# WX0_010_827DL.net
KiCad netlist of a schematic drawn in Altium Designer
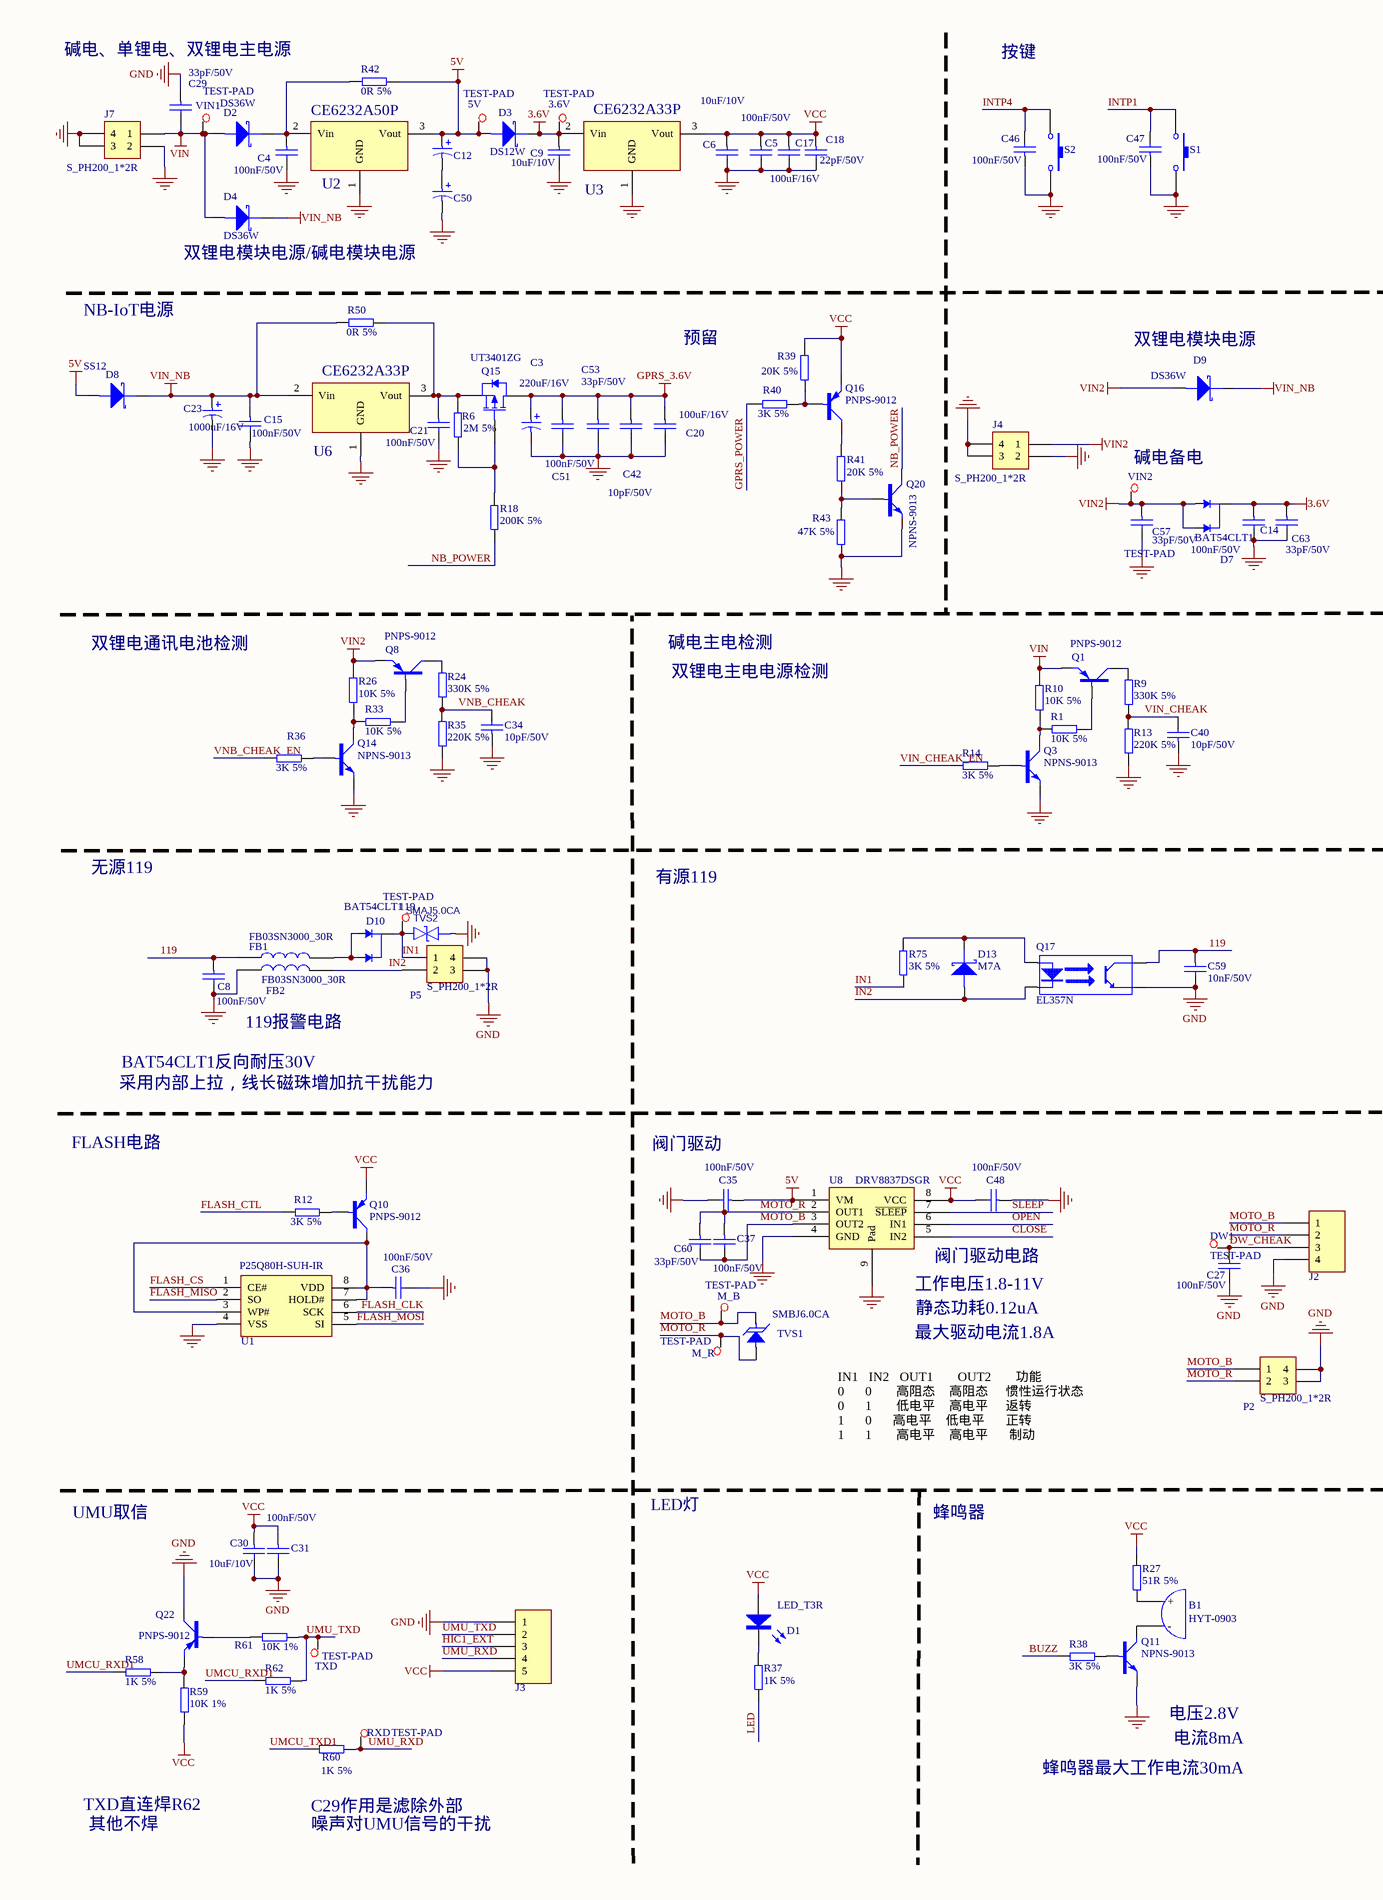
[diagram p0: WX0.010.827DL.SchDoc, left]
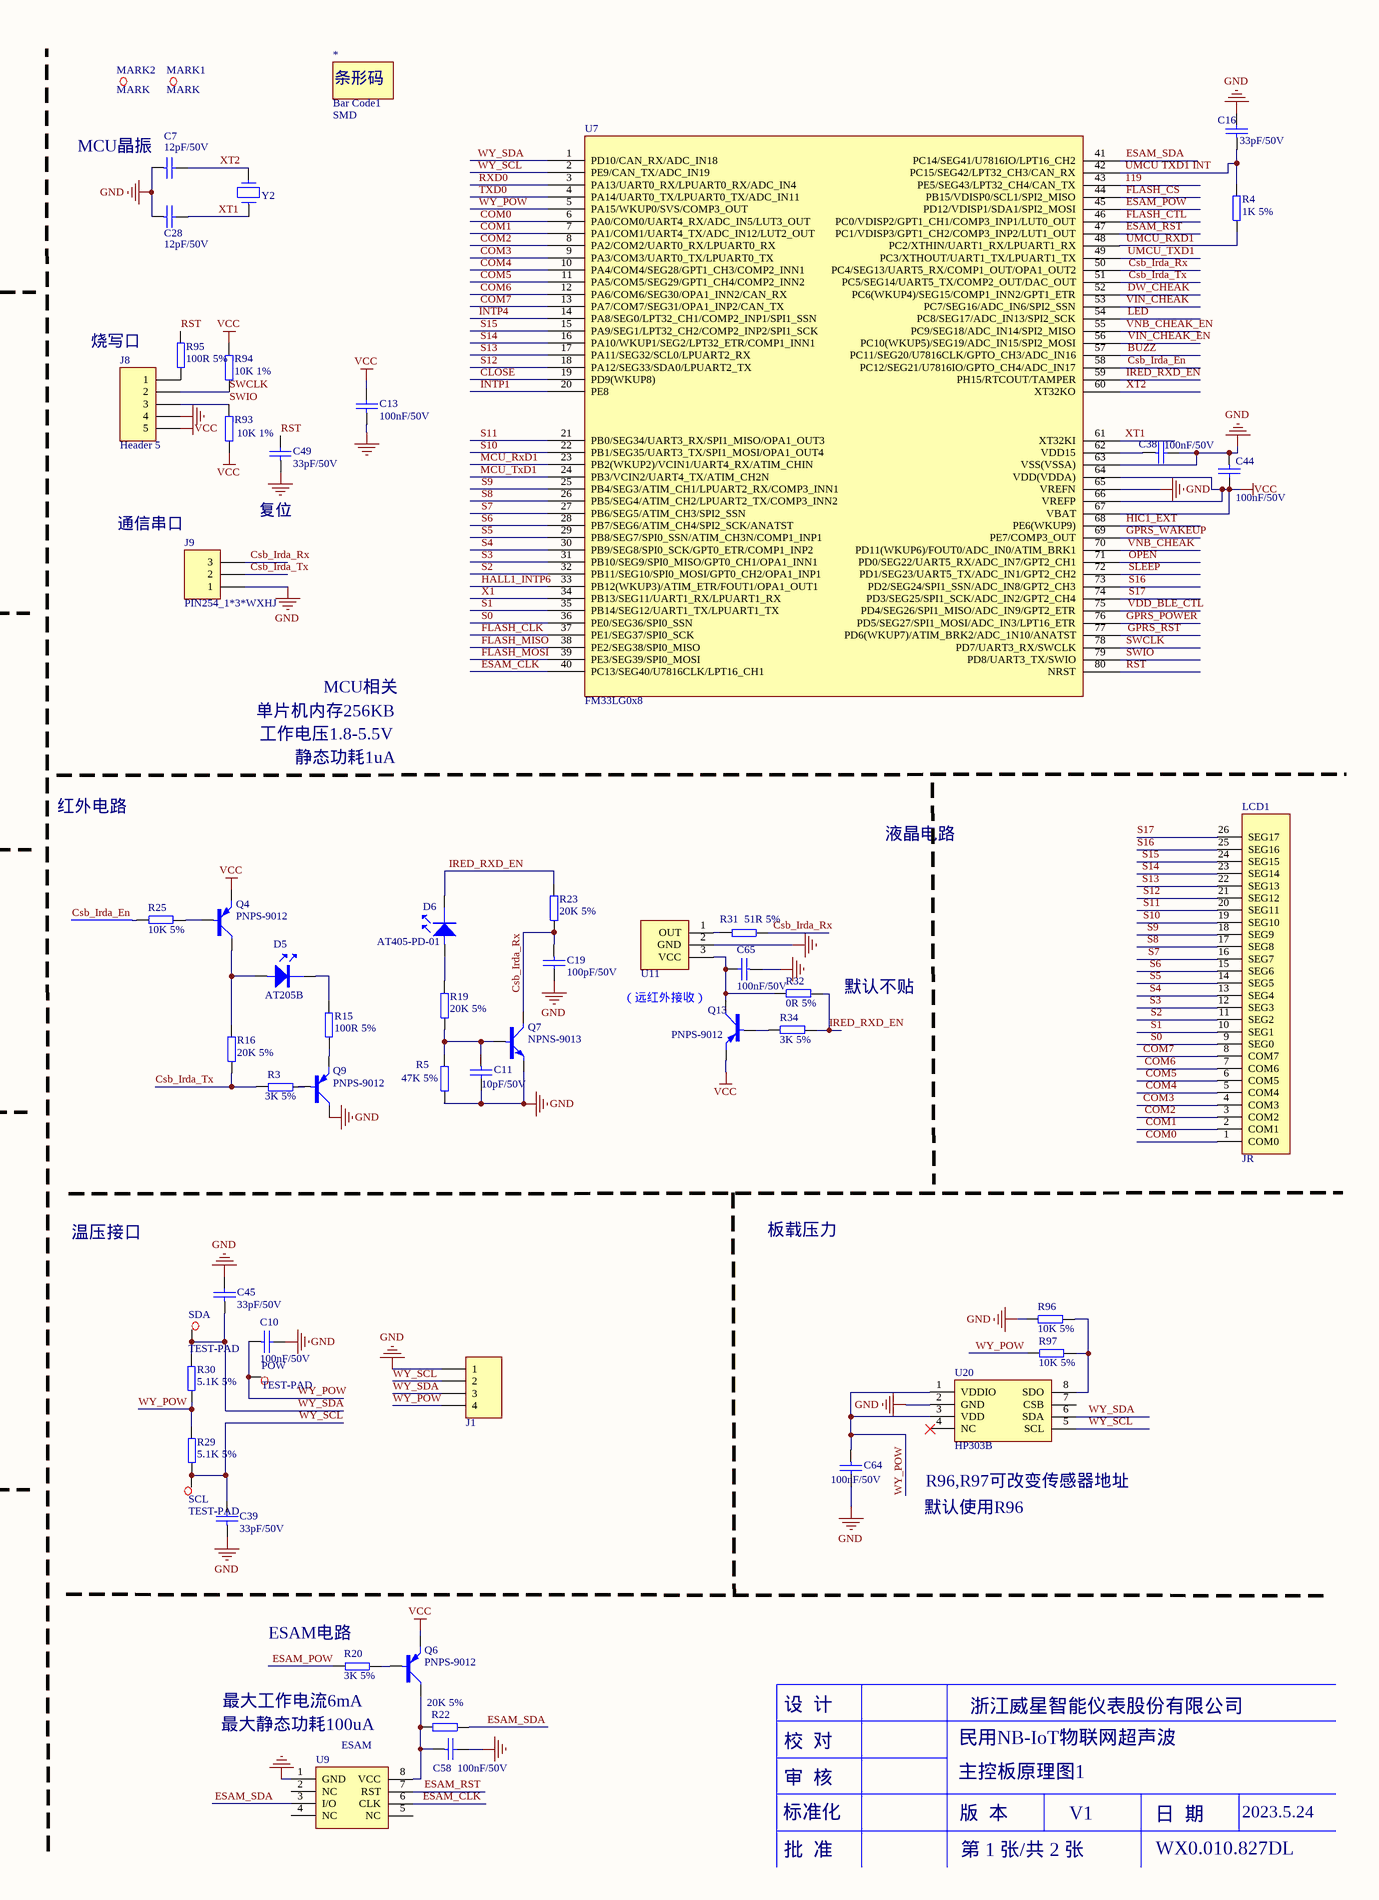
[diagram p1: WX0.010.827DL.SchDoc, right]

(export (version "E")
  (design (tool "Eeschema 10.0.6"))
  (components
    (comp (ref "*")
      (value "Bar Code1")
      (footprint "Bar Code1")
      (description "条形码 ,填充，无需焊接器件")
      (fields (field (name "PART NUMBER") "AD_WXHJ_Bar Code_02") (field (name "SMD/DIP") "SMD"))
      (libsource (lib "Database_Libs2") (part "05_AD_WXHJ_Bar Code_02"))
    )
    (comp (ref "3.6V")
      (value "TEST-PAD")
      (footprint "TEST-PAD")
      (description "单面焊盘测试点")
      (fields (field (name "PART NUMBER") "AD_WXHJ_TEST-PAD_01"))
      (libsource (lib "Database_Libs2") (part "TEST-PAD"))
    )
    (comp (ref "5V")
      (value "TEST-PAD")
      (footprint "TEST-PAD")
      (description "单面焊盘测试点")
      (fields (field (name "PART NUMBER") "AD_WXHJ_TEST-PAD_01"))
      (libsource (lib "Database_Libs2") (part "TEST-PAD"))
    )
    (comp (ref "119")
      (value "TEST-PAD")
      (footprint "TEST-PAD")
      (description "单面焊盘测试点")
      (fields (field (name "PART NUMBER") "AD_WXHJ_TEST-PAD_01"))
      (libsource (lib "Database_Libs2") (part "TEST-PAD"))
    )
    (comp (ref "B1")
      (value "HYT-0903")
      (footprint "HYT-0903")
      (description "直插,直径9mm,高5.5mm,5 V,2 V,30 mA,兴化市华宇电子有限公司,HYT-0903")
      (fields (field (name "PART NUMBER") "1010602-0007"))
      (libsource (lib "Database_Libs2") (part "07_HYT-0903"))
    )
    (comp (ref "C3")
      (value "220uF/16V")
      (footprint "220uf")
      (description "220UF")
      (fields (field (name "PART NUMBER") "1010203-0026"))
      (libsource (lib "Database_Libs2") (part "CAL7MRZLH_1000U_R"))
    )
    (comp (ref "C4")
      (value "100nF/50V")
      (footprint "CAP0603")
      (description "104pF,50 V,±10%,0603,国巨,CC0603KRX7R9BB104")
      (fields (field (name "PART NUMBER") "101020103-0021"))
      (libsource (lib "Database_Libs2") (part "CC03K7R9_100N"))
    )
    (comp (ref "C5")
      (value "100nF/50V")
      (footprint "CAP0603")
      (description "104pF,50 V,±10%,0603,国巨,CC0603KRX7R9BB104")
      (fields (field (name "PART NUMBER") "101020103-0021"))
      (libsource (lib "Database_Libs2") (part "CC03K7R9_100N"))
    )
    (comp (ref "C6")
      (value "10uF/10V")
      (footprint "CAP0603")
      (description "106pF,10 V,±10%,0603,村田,GRM188R61A106KE47D")
      (fields (field (name "PART NUMBER") "101020103-0026"))
      (libsource (lib "Database_Libs2") (part "CC03K5R6_10U"))
    )
    (comp (ref "C7")
      (value "12pF/50V")
      (footprint "CAP0603")
      (description "12P,50 V,±5%,0603,国巨,CC0603JRNPO9BN12")
      (fields (field (name "PART NUMBER") "101020103-0005"))
      (libsource (lib "Database_Libs2") (part "CC03JPO9_12P"))
    )
    (comp (ref "C8")
      (value "100nF/50V")
      (footprint "CAP0603")
      (description "104pF,50 V,±10%,0603,国巨,CC0603KRX7R9BB104")
      (fields (field (name "PART NUMBER") "101020103-0021"))
      (libsource (lib "Database_Libs2") (part "CC03K7R9_100N"))
    )
    (comp (ref "C9")
      (value "10uF/10V")
      (footprint "CAP0603")
      (description "106pF,10 V,±10%,0603,村田,GRM188R61A106KE47D")
      (fields (field (name "PART NUMBER") "101020103-0026"))
      (libsource (lib "Database_Libs2") (part "CC03K5R6_10U"))
    )
    (comp (ref "C10")
      (value "100nF/50V")
      (footprint "CAP0603")
      (description "104pF,50 V,±10%,0603,国巨,CC0603KRX7R9BB104")
      (fields (field (name "PART NUMBER") "101020103-0021"))
      (libsource (lib "Database_Libs2") (part "CC03K7R9_100N"))
    )
    (comp (ref "C11")
      (value "10pF/50V")
      (footprint "CAP0603")
      (description "10pF,50 V,±5%,0603,X7R,国巨,CC0603JRNPO9BN100")
      (fields (field (name "PART NUMBER") "101020103-0014"))
      (libsource (lib "Database_Libs2") (part "CC03JPO9_10P"))
    )
    (comp (ref "C12")
      (value "1000uF/16V")
      (footprint "CAPPC_350_800_1200")
      (description "1000uF,16 V,±20%,8*20mm,Rubycon,16ZLH1000M")
      (fields (field (name "PART NUMBER") "1010203-0029"))
      (libsource (lib "Database_Libs2") (part "CAL7MRZLH_1000U_R"))
    )
    (comp (ref "C13")
      (value "100nF/50V")
      (footprint "CAP0603")
      (description "104pF,50 V,±10%,0603,国巨,CC0603KRX7R9BB104")
      (fields (field (name "PART NUMBER") "101020103-0021"))
      (libsource (lib "Database_Libs2") (part "CC03K7R9_100N"))
    )
    (comp (ref "C14")
      (value "100nF/50V")
      (footprint "CAP0603")
      (description "104pF,50 V,±10%,0603,国巨,CC0603KRX7R9BB104")
      (fields (field (name "PART NUMBER") "101020103-0021"))
      (libsource (lib "Database_Libs2") (part "CC03K7R9_100N"))
    )
    (comp (ref "C15")
      (value "100nF/50V")
      (footprint "CAP0603")
      (description "104pF,50 V,±10%,0603,国巨,CC0603KRX7R9BB104")
      (fields (field (name "PART NUMBER") "101020103-0021"))
      (libsource (lib "Database_Libs2") (part "CC03K7R9_100N"))
    )
    (comp (ref "C16")
      (value "33pF/50V")
      (footprint "CAP0603")
      (description "33pF,50 V,±10%,0603,国巨,CC0603KRNPO9BN33")
      (fields (field (name "PART NUMBER") "101020103-0027"))
      (libsource (lib "Database_Libs2") (part "CC03KPO9_33P"))
    )
    (comp (ref "C17")
      (value "100uF/16V")
      (footprint "GRM31CR60J107ME39L")
      (description "100u,16 V,±10%,1206,国巨,CC1206KRNPO7BN106P")
      (libsource (lib "Database_Libs2") (part "CC06KPO7_106P"))
    )
    (comp (ref "C18")
      (value "22pF/50V")
      (footprint "CAP0603")
      (description "22pF,50 V,±5%,0603,国巨,CC0603JRNPO9BN22")
      (fields (field (name "PART NUMBER") "101020103-0009"))
      (libsource (lib "Database_Libs2") (part "CC03JPO9_22P"))
    )
    (comp (ref "C19")
      (value "100pF/50V")
      (footprint "CAP0603")
      (description "101pf,50 V,±5%,0603,国巨,CC0603JRNP09BN101")
      (fields (field (name "PART NUMBER") "101020103-0010"))
      (libsource (lib "Database_Libs2") (part "CC03JPO9_101P"))
    )
    (comp (ref "C20")
      (value "100uF/16V")
      (footprint "GRM31CR60J107ME39L")
      (libsource (lib "Database_Libs2") (part "CC06KPO7_106P"))
    )
    (comp (ref "C21")
      (value "100nF/50V")
      (footprint "CAP0603")
      (description "104pF,50 V,±10%,0603,国巨,CC0603KRX7R9BB104")
      (fields (field (name "PART NUMBER") "101020103-0021"))
      (libsource (lib "Database_Libs2") (part "CC03K7R9_100N"))
    )
    (comp (ref "C23")
      (value "1000uF/16V")
      (footprint "CAPSM_450_1000_1050")
      (description "1000UF,16V,±20%,贴片10*10.2MM,深圳市三炎科电子科技有限公司,16V1000UF")
      (fields (field (name "PART NUMBER") "1010203-0026"))
      (libsource (lib "Database_Libs2") (part "CAL7MRZLH_1000U_R"))
    )
    (comp (ref "C27")
      (value "100nF/50V")
      (footprint "CAP0603")
      (description "104pF,50 V,±10%,0603,国巨,CC0603KRX7R9BB104")
      (fields (field (name "PART NUMBER") "101020103-0021"))
      (libsource (lib "Database_Libs2") (part "CC03K7R9_100N"))
    )
    (comp (ref "C28")
      (value "12pF/50V")
      (footprint "CAP0603")
      (description "12P,50 V,±5%,0603,国巨,CC0603JRNPO9BN12")
      (fields (field (name "PART NUMBER") "101020103-0005"))
      (libsource (lib "Database_Libs2") (part "CC03JPO9_12P"))
    )
    (comp (ref "C29")
      (value "33pF/50V")
      (footprint "CAP0603")
      (description "33pF,50 V,±10%,0603,国巨,CC0603KRNPO9BN33")
      (fields (field (name "PART NUMBER") "101020103-0027"))
      (libsource (lib "Database_Libs2") (part "CC03KPO9_33P"))
    )
    (comp (ref "C30")
      (value "10uF/10V")
      (footprint "CAP0603")
      (description "106pF,10 V,±10%,0603,村田,GRM188R61A106KE47D")
      (fields (field (name "PART NUMBER") "101020103-0026"))
      (libsource (lib "Database_Libs2") (part "CC03K5R6_10U"))
    )
    (comp (ref "C31")
      (value "100nF/50V")
      (footprint "CAP0603")
      (description "104pF,50 V,±10%,0603,国巨,CC0603KRX7R9BB104")
      (fields (field (name "PART NUMBER") "101020103-0021"))
      (libsource (lib "Database_Libs2") (part "CC03K7R9_100N"))
    )
    (comp (ref "C34")
      (value "10pF/50V")
      (footprint "CAP0603")
      (description "10pF,50 V,±5%,0603,X7R,国巨,CC0603JRNPO9BN100")
      (fields (field (name "PART NUMBER") "101020103-0014"))
      (libsource (lib "Database_Libs2") (part "CC03JPO9_10P"))
    )
    (comp (ref "C35")
      (value "100nF/50V")
      (footprint "CAP0603")
      (description "104pF,50 V,±10%,0603,国巨,CC0603KRX7R9BB104")
      (fields (field (name "PART NUMBER") "101020103-0021"))
      (libsource (lib "Database_Libs2") (part "CC03K7R9_100N"))
    )
    (comp (ref "C36")
      (value "100nF/50V")
      (footprint "CAP0603")
      (description "104pF,50 V,±10%,0603,国巨,CC0603KRX7R9BB104")
      (fields (field (name "PART NUMBER") "101020103-0021"))
      (libsource (lib "Database_Libs2") (part "CC03K7R9_100N"))
    )
    (comp (ref "C37")
      (value "100nF/50V")
      (footprint "CAP0603")
      (description "104pF,50 V,±10%,0603,国巨,CC0603KRX7R9BB104")
      (fields (field (name "PART NUMBER") "101020103-0021"))
      (libsource (lib "Database_Libs2") (part "CC03K7R9_100N"))
    )
    (comp (ref "C38")
      (value "100nF/50V")
      (footprint "CAP0603")
      (description "104pF,50 V,±10%,0603,国巨,CC0603KRX7R9BB104")
      (fields (field (name "PART NUMBER") "101020103-0021"))
      (libsource (lib "Database_Libs2") (part "CC03K7R9_100N"))
    )
    (comp (ref "C39")
      (value "33pF/50V")
      (footprint "CAP0603")
      (description "33pF,50 V,±10%,0603,国巨,CC0603KRNPO9BN33")
      (fields (field (name "PART NUMBER") "101020103-0027"))
      (libsource (lib "Database_Libs2") (part "CC03KPO9_33P"))
    )
    (comp (ref "C40")
      (value "10pF/50V")
      (footprint "CAP0603")
      (description "10pF,50 V,±5%,0603,X7R,国巨,CC0603JRNPO9BN100")
      (fields (field (name "PART NUMBER") "101020103-0014"))
      (libsource (lib "Database_Libs2") (part "CC03JPO9_10P"))
    )
    (comp (ref "C42")
      (value "10pF/50V")
      (footprint "CAP0603")
      (description "10pF,50 V,±5%,0603,X7R,国巨,CC0603JRNPO9BN100")
      (fields (field (name "PART NUMBER") "101020103-0014"))
      (libsource (lib "Database_Libs2") (part "CC03JPO9_10P"))
    )
    (comp (ref "C44")
      (value "100nF/50V")
      (footprint "CAP0603")
      (description "104pF,50 V,±10%,0603,国巨,CC0603KRX7R9BB104")
      (fields (field (name "PART NUMBER") "101020103-0021"))
      (libsource (lib "Database_Libs2") (part "CC03K7R9_100N"))
    )
    (comp (ref "C45")
      (value "33pF/50V")
      (footprint "CAP0603")
      (description "33pF,50 V,±10%,0603,国巨,CC0603KRNPO9BN33")
      (fields (field (name "PART NUMBER") "101020103-0027"))
      (libsource (lib "Database_Libs2") (part "CC03KPO9_33P"))
    )
    (comp (ref "C46")
      (value "100nF/50V")
      (footprint "CAP0603")
      (description "104pF,50 V,±10%,0603,国巨,CC0603KRX7R9BB104")
      (fields (field (name "PART NUMBER") "101020103-0021"))
      (libsource (lib "Database_Libs2") (part "CC03K7R9_100N"))
    )
    (comp (ref "C47")
      (value "100nF/50V")
      (footprint "CAP0603")
      (description "104pF,50 V,±10%,0603,国巨,CC0603KRX7R9BB104")
      (fields (field (name "PART NUMBER") "101020103-0021"))
      (libsource (lib "Database_Libs2") (part "CC03K7R9_100N"))
    )
    (comp (ref "C48")
      (value "100nF/50V")
      (footprint "CAP0603")
      (description "104pF,50 V,±10%,0603,国巨,CC0603KRX7R9BB104")
      (fields (field (name "PART NUMBER") "101020103-0021"))
      (libsource (lib "Database_Libs2") (part "CC03K7R9_100N"))
    )
    (comp (ref "C49")
      (value "33pF/50V")
      (footprint "CAP0603")
      (description "33pF,50 V,±10%,0603,国巨,CC0603KRNPO9BN33")
      (fields (field (name "PART NUMBER") "101020103-0027"))
      (libsource (lib "Database_Libs2") (part "CC03KPO9_33P"))
    )
    (comp (ref "C50")
      (value "1000uF/16V")
      (footprint "CAPPC_350_800_1200")
      (description "1000uF,16 V,±20%,8*20mm,Rubycon,16ZLH1000M")
      (fields (field (name "PART NUMBER") "1010203-0029"))
      (libsource (lib "Database_Libs2") (part "CAL7MRZLH_1000U_R"))
    )
    (comp (ref "C51")
      (value "100nF/50V")
      (footprint "CAP0603")
      (description "104pF,50 V,±10%,0603,国巨,CC0603KRX7R9BB104")
      (fields (field (name "PART NUMBER") "101020103-0021"))
      (libsource (lib "Database_Libs2") (part "CC03K7R9_100N"))
    )
    (comp (ref "C53")
      (value "33pF/50V")
      (footprint "CAP0603")
      (description "33pF,50 V,±10%,0603,国巨,CC0603KRNPO9BN33")
      (fields (field (name "PART NUMBER") "101020103-0027"))
      (libsource (lib "Database_Libs2") (part "CC03KPO9_33P"))
    )
    (comp (ref "C57")
      (value "33pF/50V")
      (footprint "CAP0603")
      (description "33pF,50 V,±10%,0603,国巨,CC0603KRNPO9BN33")
      (fields (field (name "PART NUMBER") "101020103-0027"))
      (libsource (lib "Database_Libs2") (part "CC03KPO9_33P"))
    )
    (comp (ref "C58")
      (value "100nF/50V")
      (footprint "CAP0603")
      (description "104pF,50 V,±10%,0603,国巨,CC0603KRX7R9BB104")
      (fields (field (name "PART NUMBER") "101020103-0021"))
      (libsource (lib "Database_Libs2") (part "CC03K7R9_100N"))
    )
    (comp (ref "C59")
      (value "10nF/50V")
      (footprint "CAP0603")
      (description "10nF,50 V,±10%,0603,X7R,国巨,CC0603KRX7R9BB103")
      (fields (field (name "PART NUMBER") "101020103-0007"))
      (libsource (lib "Database_Libs2") (part "CC03K7R9_103P"))
    )
    (comp (ref "C60")
      (value "33pF/50V")
      (footprint "CAP0603")
      (description "33pF,50 V,±10%,0603,国巨,CC0603KRNPO9BN33")
      (fields (field (name "PART NUMBER") "101020103-0027"))
      (libsource (lib "Database_Libs2") (part "CC03KPO9_33P"))
    )
    (comp (ref "C63")
      (value "33pF/50V")
      (footprint "CAP0603")
      (description "33pF,50 V,±10%,0603,国巨,CC0603KRNPO9BN33")
      (fields (field (name "PART NUMBER") "101020103-0027"))
      (libsource (lib "Database_Libs2") (part "CC03KPO9_33P"))
    )
    (comp (ref "C64")
      (value "100nF/50V")
      (footprint "CAP0603")
      (description "104pF,50 V,±10%,0603,国巨,CC0603KRX7R9BB104")
      (fields (field (name "PART NUMBER") "101020103-0021"))
      (libsource (lib "Database_Libs2") (part "CC03K7R9_100N"))
    )
    (comp (ref "C65")
      (value "100nF/50V")
      (footprint "CAP0603")
      (description "104pF,50 V,±10%,0603,国巨,CC0603KRX7R9BB104")
      (fields (field (name "PART NUMBER") "101020103-0021"))
      (libsource (lib "Database_Libs2") (part "CC03K7R9_100N"))
    )
    (comp (ref "D1")
      (value "LED_T3R")
      (footprint "LED2_300")
      (description "圆形插件,3mm 圆形,插件,红光,湖北匡通电子有限公司,3BB4HC")
      (fields (field (name "PART NUMBER") "101040102-0001"))
      (libsource (lib "Database_Libs2") (part "01-LED_T3R"))
    )
    (comp (ref "D2")
      (value "DS36W")
      (footprint "SOD-123FL")
      (description "DS36W,SOD123-FL,3 A,42 V,60 V,浙江领晨科技有限公司,DS36W")
      (fields (field (name "PART NUMBER") "101040101-0055"))
      (libsource (lib "Database_Libs2") (part "02_DS12W"))
    )
    (comp (ref "D3")
      (value "DS12W")
      (footprint "SOD-123FL")
      (description "DS12W,SOD-123FL,1 A,0.55 V,20 V,领晨科技,DS12W")
      (fields (field (name "PART NUMBER") "101040101-0048"))
      (libsource (lib "Database_Libs2") (part "02_DS12W"))
    )
    (comp (ref "D4")
      (value "DS36W")
      (footprint "SOD-123FL")
      (description "DS36W,SOD123-FL,3 A,42 V,60 V,浙江领晨科技有限公司,DS36W")
      (fields (field (name "PART NUMBER") "101040101-0055"))
      (libsource (lib "Database_Libs2") (part "02_DS36W"))
    )
    (comp (ref "D5")
      (value "AT205B")
      (footprint "IR_254_1000_500")
      (description "直插,Φ5.8mm圆头透明色，,0.1 A,4 V,5 V,上海品观电子有限公司,AT205B")
      (fields (field (name "PART NUMBER") "101040101-0034"))
      (libsource (lib "Database_Libs2") (part "01_AT205B"))
    )
    (comp (ref "D6")
      (value "AT405-PD-01")
      (footprint "IR_254_1000_500")
      (description "Φ5.8mm圆头黑色，光电接收管,Φ5.8mm,0.01 A,1.2 V,60 V,上海品观电子,AT405-PD-01")
      (fields (field (name "PART NUMBER") "101040101-0035"))
      (libsource (lib "Database_Libs2") (part "01_AT405-PD-01"))
    )
    (comp (ref "D7")
      (value "BAT54CLT1")
      (footprint "SOT-23")
      (description "BAT54CLT1，SOT23-3,SOT23-3,0.2 A,0.8 V,30 V,安森美,BAT54CLT1")
      (fields (field (name "PART NUMBER") "101040101-0038"))
      (libsource (lib "Database_Libs2") (part "02_BAT54CLT1"))
    )
    (comp (ref "D8")
      (value "SS12")
      (footprint "DO-214AC")
      (description "SS12,DO-214AC,1 A,0.55 V,20 V,昶鑫,SS12")
      (fields (field (name "PART NUMBER") "101040101-0009"))
      (libsource (lib "Database_Libs2") (part "02_SS12"))
    )
    (comp (ref "D9")
      (value "DS36W")
      (footprint "SOD-123FL")
      (description "DS36W,SOD123-FL,3 A,42 V,60 V,浙江领晨科技有限公司,DS36W")
      (fields (field (name "PART NUMBER") "101040101-0055"))
      (libsource (lib "Database_Libs2") (part "02_DS36W"))
    )
    (comp (ref "D10")
      (value "BAT54CLT1")
      (footprint "SOT-23")
      (description "BAT54CLT1，SOT23-3,SOT23-3,0.2 A,0.8 V,30 V,安森美,BAT54CLT1")
      (fields (field (name "PART NUMBER") "101040101-0038"))
      (libsource (lib "Database_Libs2") (part "02_BAT54CLT1"))
    )
    (comp (ref "D13")
      (value "M7A")
      (footprint "DO-214AC")
      (description "M7A,DO-214AC,1 A,1.1 V,1000 V,杭州闽达电子有限公司,M7A")
      (fields (field (name "PART NUMBER") "101040101-0008"))
      (libsource (lib "Database_Libs2") (part "02_M7A"))
    )
    (comp (ref "DW1")
      (value "TEST-PAD")
      (footprint "TEST-PAD")
      (description "单面焊盘测试点")
      (fields (field (name "PART NUMBER") "AD_WXHJ_TEST-PAD_01"))
      (libsource (lib "Database_Libs2") (part "TEST-PAD"))
    )
    (comp (ref "FB1")
      (value "FB03SN3000_30R")
      (footprint "IND0603")
      (description "chilisin(奇力新),0603,30Ω ±25% @100MHz,150 V,125 ℃,PBY160808T-300Y-N,-55 ℃,不含铅,,,圆盘,30Ω ±25% @100MHz")
      (fields (field (name "PART NUMBER") "109010101-0003"))
      (libsource (lib "Database_Libs2") (part "06_FB03SN3000_30R"))
    )
    (comp (ref "FB2")
      (value "FB03SN3000_30R")
      (footprint "IND0603")
      (description "chilisin(奇力新),0603,30Ω ±25% @100MHz,150 V,125 ℃,PBY160808T-300Y-N,-55 ℃,不含铅,,,圆盘,30Ω ±25% @100MHz")
      (fields (field (name "PART NUMBER") "109010101-0003"))
      (libsource (lib "Database_Libs2") (part "06_FB03SN3000_30R"))
    )
    (comp (ref "J1")
      (value "SMT-1.5-4")
      (footprint "CONN-SMD_4P-P1.5_HCTL_HC-ZH-4PLT")
      (description "4针1.5mm间距，贴片卧式,9.0mm*6.5mm,公头,单排,4针1.5mm间距，贴片卧式")
      (fields (field (name "PART NUMBER") "1010902-0126"))
      (libsource (lib "Database_Libs2") (part "温压接口"))
    )
    (comp (ref "J2")
      (value "SMT-1.5-4")
      (footprint "CONN-SMD_4P-P1.25_HCTL_HC-1.25-4PLT")
      (description "4针1.5mm间距，贴片卧式,9.0mm*6.5mm,公头,单排,4针1.5mm间距，贴片卧式")
      (fields (field (name "PART NUMBER") "1010902-0126"))
      (libsource (lib "Database_Libs2") (part "温压接口"))
    )
    (comp (ref "J3")
      (value "SMT-1.25-5")
      (footprint "CONN-SMD_5P-P1.25_HCTL_HC-1.25-5PLT")
      (description "1.25-5AWR 卷,5针1.25mm,母头,单排,贴片卧式")
      (fields (field (name "PART NUMBER") "1010902-0122"))
      (libsource (lib "Database_Libs2") (part "UMU接口"))
    )
    (comp (ref "J4")
      (value "S_PH200_1*2R")
      (footprint "CONN-SMD_2.0-2PLT")
      (description "PH2.0_2AWR 卧,贴片卧式,母头,单排,2针2.0mm")
      (fields (field (name "PART NUMBER") "1010902-0125"))
      (libsource (lib "") (part "S_PH200_1*2R_1"))
    )
    (comp (ref "J7")
      (value "S_PH200_1*2R")
      (footprint "2*2.5立贴")
      (description "PH2.0_2AWR 卧,贴片卧式,母头,单排,2针2.0mm")
      (fields (field (name "PART NUMBER") "1010902-0125"))
      (libsource (lib "") (part "S_PH200_1*2R_1"))
    )
    (comp (ref "J8")
      (value "Header 5")
      (footprint "PIN254_1*5SR")
      (description "Header, 5-Pin")
      (libsource (lib "CBB_Lib_SCH") (part "Header 5"))
    )
    (comp (ref "J9")
      (value "PIN254_1*3*WXHJ")
      (footprint "PIN254_1*3*WXHJ")
      (description "1*3 ，Φ1.0 ，2.54mm，直脚,无需焊接器件")
      (fields (field (name "PART NUMBER") "AD_WXHJ_PinHeader_04"))
      (libsource (lib "Database_Libs2") (part "PIN254_1*3*WXHJ"))
    )
    (comp (ref "LCD1") (value "JR") (footprint "JR-H26263ARP") (libsource (lib "未添加") (part "JR")))
    (comp (ref "MARK1")
      (value "MARK")
      (footprint "MARK")
      (description "MARK点")
      (fields (field (name "PART NUMBER") "AD_WXHJ_MARK_01"))
      (libsource (lib "Database_Libs2") (part "MARK"))
    )
    (comp (ref "MARK2")
      (value "MARK")
      (footprint "MARK")
      (description "MARK点")
      (fields (field (name "PART NUMBER") "AD_WXHJ_MARK_01"))
      (libsource (lib "Database_Libs2") (part "MARK"))
    )
    (comp (ref "M_B")
      (value "TEST-PAD")
      (footprint "TEST-PAD")
      (description "单面焊盘测试点")
      (fields (field (name "PART NUMBER") "AD_WXHJ_TEST-PAD_01"))
      (libsource (lib "Database_Libs2") (part "TEST-PAD"))
    )
    (comp (ref "M_R")
      (value "TEST-PAD")
      (footprint "TEST-PAD")
      (description "单面焊盘测试点")
      (fields (field (name "PART NUMBER") "AD_WXHJ_TEST-PAD_01"))
      (libsource (lib "Database_Libs2") (part "TEST-PAD"))
    )
    (comp (ref "P2")
      (value "S_PH200_1*2R")
      (footprint "CONN-SMD_2.0-2PLT")
      (description "PH2.0_2AWR 卧,贴片卧式,母头,单排,2针2.0mm")
      (fields (field (name "PART NUMBER") "1010902-0125"))
      (libsource (lib "Database_Libs2") (part "S_PH200_1*2R"))
    )
    (comp (ref "P5")
      (value "S_PH200_1*2R")
      (footprint "CONN-SMD_2.0-2PLT")
      (description "PH2.0_2AWR 卧,贴片卧式,母头,单排,2针2.0mm")
      (fields (field (name "PART NUMBER") "1010902-0125"))
      (libsource (lib "Database_Libs2") (part "S_PH200_1*2R"))
    )
    (comp (ref "POW")
      (value "TEST-PAD")
      (footprint "TEST-PAD")
      (description "单面焊盘测试点")
      (fields (field (name "PART NUMBER") "AD_WXHJ_TEST-PAD_01"))
      (libsource (lib "Database_Libs2") (part "TEST-PAD"))
    )
    (comp (ref "Q1")
      (value "PNPS-9012")
      (footprint "SOT-23")
      (description "9012,PNP,SOT-23,JCET;长电,S9012")
      (fields (field (name "PART NUMBER") "101040201-0001"))
      (libsource (lib "Database_Libs2") (part "03_PNPS-9012"))
    )
    (comp (ref "Q3")
      (value "NPNS-9013")
      (footprint "SOT-23")
      (description "9013,NPN,SOT-23,长电,S9013")
      (fields (field (name "PART NUMBER") "101040201-0002"))
      (libsource (lib "Database_Libs2") (part "03_NPNS-9013"))
    )
    (comp (ref "Q4")
      (value "PNPS-9012")
      (footprint "SOT-23")
      (description "9012,PNP,SOT-23,JCET;长电,S9012")
      (fields (field (name "PART NUMBER") "101040201-0001"))
      (libsource (lib "Database_Libs2") (part "03_PNPS-9012"))
    )
    (comp (ref "Q6")
      (value "PNPS-9012")
      (footprint "SOT-23")
      (description "9012,PNP,SOT-23,JCET;长电,S9012")
      (fields (field (name "PART NUMBER") "101040201-0001"))
      (libsource (lib "Database_Libs2") (part "03_PNPS-9012"))
    )
    (comp (ref "Q7")
      (value "NPNS-9013")
      (footprint "SOT-23")
      (description "9013,NPN,SOT-23,长电,S9013")
      (fields (field (name "PART NUMBER") "101040201-0002"))
      (libsource (lib "Database_Libs2") (part "03_NPNS-9013"))
    )
    (comp (ref "Q8")
      (value "PNPS-9012")
      (footprint "SOT-23")
      (description "9012,PNP,SOT-23,JCET;长电,S9012")
      (fields (field (name "PART NUMBER") "101040201-0001"))
      (libsource (lib "Database_Libs2") (part "03_PNPS-9012"))
    )
    (comp (ref "Q9")
      (value "PNPS-9012")
      (footprint "SOT-23")
      (description "9012,PNP,SOT-23,JCET;长电,S9012")
      (fields (field (name "PART NUMBER") "101040201-0001"))
      (libsource (lib "Database_Libs2") (part "03_PNPS-9012"))
    )
    (comp (ref "Q10")
      (value "PNPS-9012")
      (footprint "SOT-23")
      (description "9012,PNP,SOT-23,JCET;长电,S9012")
      (fields (field (name "PART NUMBER") "101040201-0001"))
      (libsource (lib "Database_Libs2") (part "03_PNPS-9012"))
    )
    (comp (ref "Q11")
      (value "NPNS-9013")
      (footprint "SOT-23")
      (description "9013,NPN,SOT-23,长电,S9013")
      (fields (field (name "PART NUMBER") "101040201-0002"))
      (libsource (lib "Database_Libs2") (part "03_NPNS-9013"))
    )
    (comp (ref "Q13")
      (value "PNPS-9012")
      (footprint "SOT-23")
      (description "9012,PNP,SOT-23,JCET;长电,S9012")
      (fields (field (name "PART NUMBER") "101040201-0001"))
      (libsource (lib "Database_Libs2") (part "03_PNPS-9012"))
    )
    (comp (ref "Q14")
      (value "NPNS-9013")
      (footprint "SOT-23")
      (description "9013,NPN,SOT-23,长电,S9013")
      (fields (field (name "PART NUMBER") "101040201-0002"))
      (libsource (lib "Database_Libs2") (part "03_NPNS-9013"))
    )
    (comp (ref "Q15")
      (value "UT3401ZG")
      (footprint "SOT-23")
      (description "UT3401ZG,P-MOS,SOT-23,UTC,UT3401ZG")
      (fields (field (name "PART NUMBER") "101040201-0013"))
      (libsource (lib "Database_Libs2") (part "03_P-UT3401ZG"))
    )
    (comp (ref "Q16")
      (value "PNPS-9012")
      (footprint "SOT-23")
      (description "9012,PNP,SOT-23,JCET;长电,S9012")
      (fields (field (name "PART NUMBER") "101040201-0001"))
      (libsource (lib "Database_Libs2") (part "03_PNPS-9012"))
    )
    (comp (ref "Q17")
      (value "EL357N")
      (footprint "EL357D")
      (description "SOP4,贴片,ELERLIGHT,EL357N(D)(TA)-G")
      (fields (field (name "PART NUMBER") "1010502-0045"))
      (libsource (lib "Database_Libs2") (part "01_EL357N9(D)(TA)-G"))
    )
    (comp (ref "Q20")
      (value "NPNS-9013")
      (footprint "SOT-23")
      (description "9013,NPN,SOT-23,长电,S9013")
      (fields (field (name "PART NUMBER") "101040201-0002"))
      (libsource (lib "Database_Libs2") (part "03_NPNS-9013"))
    )
    (comp (ref "Q22")
      (value "PNPS-9012")
      (footprint "SOT-23")
      (description "9012,PNP,SOT-23,JCET;长电,S9012")
      (fields (field (name "PART NUMBER") "101040201-0001"))
      (libsource (lib "Database_Libs2") (part "03_PNPS-9012"))
    )
    (comp (ref "R1")
      (value "10K 5%")
      (footprint "RES0603")
      (description "国巨,±5%,0603,,155 ℃,-55 ℃,RC0603JR-0710KL,无铅,200 ppm/℃,1/10W,,10K")
      (fields (field (name "PART NUMBER") "101010103-0003"))
      (libsource (lib "Database_Libs2") (part "RC03J_10K"))
    )
    (comp (ref "R3")
      (value "3K 5%")
      (footprint "RES0603")
      (description "国巨,±5%,0603,,155 ℃,-55 ℃,RC0603JR-073KL,无铅,100 ppm/℃,1/10W,,3K")
      (fields (field (name "PART NUMBER") "101010103-0006"))
      (libsource (lib "Database_Libs2") (part "RC03J_3K"))
    )
    (comp (ref "R4")
      (value "1K 5%")
      (footprint "RES0603")
      (description "1K,±5%,1/10W,0603,国巨,RC0603JR-071KL")
      (fields (field (name "PART NUMBER") "101010103-0008"))
      (libsource (lib "Database_Libs2") (part "RC03J_1K"))
    )
    (comp (ref "R5")
      (value "47K 5%")
      (footprint "RES0603")
      (description "47K,±5%,1/10W,0603,国巨,RC0603JR-0747KL")
      (fields (field (name "PART NUMBER") "101010103-0012"))
      (libsource (lib "Database_Libs2") (part "RC03J_47K"))
    )
    (comp (ref "R6")
      (value "2M 5%")
      (footprint "RES0603")
      (description "国巨,±5%,0603,,155 ℃,-55 ℃,RC0603JR-072ML,含铅,100 ppm/℃,1/10W,,2M")
      (fields (field (name "PART NUMBER") "101010103-0025"))
      (libsource (lib "Database_Libs2") (part "RC03J_2M"))
    )
    (comp (ref "R9")
      (value "330K 5%")
      (footprint "RES0603")
      (description "330K,±5%,1/10W,0603,国巨,RC0603JR-07330KL")
      (fields (field (name "PART NUMBER") "101010103-0066"))
      (libsource (lib "Database_Libs2") (part "RC03J_330K"))
    )
    (comp (ref "R10")
      (value "10K 5%")
      (footprint "RES0603")
      (description "国巨,±5%,0603,,155 ℃,-55 ℃,RC0603JR-0710KL,无铅,200 ppm/℃,1/10W,,10K")
      (fields (field (name "PART NUMBER") "101010103-0003"))
      (libsource (lib "Database_Libs2") (part "RC03J_10K"))
    )
    (comp (ref "R12")
      (value "3K 5%")
      (footprint "RES0603")
      (description "国巨,±5%,0603,,155 ℃,-55 ℃,RC0603JR-073KL,无铅,100 ppm/℃,1/10W,,3K")
      (fields (field (name "PART NUMBER") "101010103-0006"))
      (libsource (lib "Database_Libs2") (part "RC03J_3K"))
    )
    (comp (ref "R13")
      (value "220K 5%")
      (footprint "RES0603")
      (description "220K,±5%,1/10W,0603,国巨,RC0603JR-07220KL")
      (fields (field (name "PART NUMBER") "101010103-0044"))
      (libsource (lib "Database_Libs2") (part "RC03J_220K"))
    )
    (comp (ref "R14")
      (value "3K 5%")
      (footprint "RES0603")
      (description "国巨,±5%,0603,,155 ℃,-55 ℃,RC0603JR-073KL,无铅,100 ppm/℃,1/10W,,3K")
      (fields (field (name "PART NUMBER") "101010103-0006"))
      (libsource (lib "Database_Libs2") (part "RC03J_3K"))
    )
    (comp (ref "R15")
      (value "100R 5%")
      (footprint "RES0603")
      (description "100R,±5%,1/10W,0603,国巨,RC0603JR-07100RL")
      (fields (field (name "PART NUMBER") "101010103-0022"))
      (libsource (lib "Database_Libs2") (part "RC03J_100R"))
    )
    (comp (ref "R16")
      (value "20K 5%")
      (footprint "RES0603")
      (description "国巨,±5%,0603,,155 ℃,-55 ℃,RC0603JR-0720KL,无铅,200 ppm/℃,1/10W,,20K")
      (fields (field (name "PART NUMBER") "101010103-0004"))
      (libsource (lib "Database_Libs2") (part "RC03J_20K"))
    )
    (comp (ref "R18")
      (value "200K 5%")
      (footprint "RES0603")
      (description "200K,±5%,1/10W,0603,国巨,RC0603JR-07200KL")
      (fields (field (name "PART NUMBER") "101010103-0034"))
      (libsource (lib "Database_Libs2") (part "RC03J_200K"))
    )
    (comp (ref "R19")
      (value "20K 5%")
      (footprint "RES0603")
      (description "国巨,±5%,0603,,155 ℃,-55 ℃,RC0603JR-0720KL,无铅,200 ppm/℃,1/10W,,20K")
      (fields (field (name "PART NUMBER") "101010103-0004"))
      (libsource (lib "Database_Libs2") (part "RC03J_20K"))
    )
    (comp (ref "R20")
      (value "3K 5%")
      (footprint "RES0603")
      (description "国巨,±5%,0603,,155 ℃,-55 ℃,RC0603JR-0710KL,无铅,200 ppm/℃,1/10W,,10K")
      (fields (field (name "PART NUMBER") "101010103-0003"))
      (libsource (lib "Database_Libs2") (part "RC03J_10K"))
    )
    (comp (ref "R22")
      (value "20K 5%")
      (footprint "RES0603")
      (description "国巨,±5%,0603,,155 ℃,-55 ℃,RC0603JR-0720KL,无铅,200 ppm/℃,1/10W,,20K")
      (fields (field (name "PART NUMBER") "101010103-0004"))
      (libsource (lib "Database_Libs2") (part "RC03J_20K"))
    )
    (comp (ref "R23")
      (value "20K 5%")
      (footprint "RES0603")
      (description "国巨,±5%,0603,,155 ℃,-55 ℃,RC0603JR-0720KL,无铅,200 ppm/℃,1/10W,,20K")
      (fields (field (name "PART NUMBER") "101010103-0004"))
      (libsource (lib "Database_Libs2") (part "RC03J_20K"))
    )
    (comp (ref "R24")
      (value "330K 5%")
      (footprint "RES0603")
      (description "330K,±5%,1/10W,0603,国巨,RC0603JR-07330KL")
      (fields (field (name "PART NUMBER") "101010103-0066"))
      (libsource (lib "Database_Libs2") (part "RC03J_330K"))
    )
    (comp (ref "R25")
      (value "10K 5%")
      (footprint "RES0603")
      (description "国巨,±5%,0603,,155 ℃,-55 ℃,RC0603JR-0710KL,无铅,200 ppm/℃,1/10W,,10K")
      (fields (field (name "PART NUMBER") "101010103-0003"))
      (libsource (lib "Database_Libs2") (part "RC03J_10K"))
    )
    (comp (ref "R26")
      (value "10K 5%")
      (footprint "RES0603")
      (description "国巨,±5%,0603,,155 ℃,-55 ℃,RC0603JR-0710KL,无铅,200 ppm/℃,1/10W,,10K")
      (fields (field (name "PART NUMBER") "101010103-0003"))
      (libsource (lib "Database_Libs2") (part "RC03J_10K"))
    )
    (comp (ref "R27")
      (value "51R 5%")
      (footprint "RES0603")
      (description "国巨,±5%,0603,,155 ℃,-55 ℃,RC0603JR-0751RL,无铅,100 ppm/℃,1/10W,,51欧")
      (fields (field (name "PART NUMBER") "101010103-0037"))
      (libsource (lib "Database_Libs2") (part "RC03J_51R"))
    )
    (comp (ref "R29")
      (value "5.1K 5%")
      (footprint "RES0603")
      (description "国巨,±5%,0603,,155 ℃,55 ℃,RC0603JR-075.1KL,无铅,200 ppm/℃,1/10W,,5.1k")
      (fields (field (name "PART NUMBER") "101010103-0015"))
      (libsource (lib "Database_Libs2") (part "RC03J_5.1K"))
    )
    (comp (ref "R30")
      (value "5.1K 5%")
      (footprint "RES0603")
      (description "国巨,±5%,0603,,155 ℃,55 ℃,RC0603JR-075.1KL,无铅,200 ppm/℃,1/10W,,5.1k")
      (fields (field (name "PART NUMBER") "101010103-0015"))
      (libsource (lib "Database_Libs2") (part "RC03J_5.1K"))
    )
    (comp (ref "R31")
      (value "51R 5%")
      (footprint "RES0603")
      (description "国巨,±5%,0603,,155 ℃,-55 ℃,RC0603JR-0751RL,无铅,100 ppm/℃,1/10W,,51欧")
      (fields (field (name "PART NUMBER") "101010103-0037"))
      (libsource (lib "Database_Libs2") (part "RC03J_51R"))
    )
    (comp (ref "R32")
      (value "0R 5%")
      (footprint "RES0603")
      (description "国巨,±5%,0603,,155 ℃,-55 ℃,RC0603J2-070RL,无铅,200 ppm/℃,1/10W,,0R")
      (fields (field (name "PART NUMBER") "101010103-0001"))
      (libsource (lib "Database_Libs2") (part "RC03J_0R"))
    )
    (comp (ref "R33")
      (value "10K 5%")
      (footprint "RES0603")
      (description "国巨,±5%,0603,,155 ℃,-55 ℃,RC0603JR-0710KL,无铅,200 ppm/℃,1/10W,,10K")
      (fields (field (name "PART NUMBER") "101010103-0003"))
      (libsource (lib "Database_Libs2") (part "RC03J_10K"))
    )
    (comp (ref "R34")
      (value "3K 5%")
      (footprint "RES0603")
      (description "国巨,±5%,0603,,155 ℃,-55 ℃,RC0603JR-073KL,无铅,100 ppm/℃,1/10W,,3K")
      (fields (field (name "PART NUMBER") "101010103-0006"))
      (libsource (lib "Database_Libs2") (part "RC03J_3K"))
    )
    (comp (ref "R35")
      (value "220K 5%")
      (footprint "RES0603")
      (description "220K,±5%,1/10W,0603,国巨,RC0603JR-07220KL")
      (fields (field (name "PART NUMBER") "101010103-0044"))
      (libsource (lib "Database_Libs2") (part "RC03J_220K"))
    )
    (comp (ref "R36")
      (value "3K 5%")
      (footprint "RES0603")
      (description "国巨,±5%,0603,,155 ℃,-55 ℃,RC0603JR-073KL,无铅,100 ppm/℃,1/10W,,3K")
      (fields (field (name "PART NUMBER") "101010103-0006"))
      (libsource (lib "Database_Libs2") (part "RC03J_3K"))
    )
    (comp (ref "R37")
      (value "1K 5%")
      (footprint "RES0603")
      (description "1K,±5%,1/10W,0603,国巨,RC0603JR-071KL")
      (fields (field (name "PART NUMBER") "101010103-0008"))
      (libsource (lib "Database_Libs2") (part "RC03J_1K"))
    )
    (comp (ref "R38")
      (value "3K 5%")
      (footprint "RES0603")
      (description "国巨,±5%,0603,,155 ℃,-55 ℃,RC0603JR-073KL,无铅,100 ppm/℃,1/10W,,3K")
      (fields (field (name "PART NUMBER") "101010103-0006"))
      (libsource (lib "Database_Libs2") (part "RC03J_3K"))
    )
    (comp (ref "R39")
      (value "20K 5%")
      (footprint "RES0603")
      (description "国巨,±5%,0603,,155 ℃,-55 ℃,RC0603JR-0720KL,无铅,200 ppm/℃,1/10W,,20K")
      (fields (field (name "PART NUMBER") "101010103-0004"))
      (libsource (lib "Database_Libs2") (part "RC03J_20K"))
    )
    (comp (ref "R40")
      (value "3K 5%")
      (footprint "RES0603")
      (description "国巨,±5%,0603,,155 ℃,-55 ℃,RC0603JR-073KL,无铅,100 ppm/℃,1/10W,,3K")
      (fields (field (name "PART NUMBER") "101010103-0006"))
      (libsource (lib "Database_Libs2") (part "RC03J_3K"))
    )
    (comp (ref "R41")
      (value "20K 5%")
      (footprint "RES0603")
      (description "国巨,±5%,0603,,155 ℃,-55 ℃,RC0603JR-0720KL,无铅,200 ppm/℃,1/10W,,20K")
      (fields (field (name "PART NUMBER") "101010103-0004"))
      (libsource (lib "Database_Libs2") (part "RC03J_20K"))
    )
    (comp (ref "R42")
      (value "0R 5%")
      (footprint "RES1206")
      (description "0Ω,±5%,1/4W,1206,国巨,RC1206JR-070RL")
      (fields (field (name "PART NUMBER") "101010101-0013"))
      (libsource (lib "Database_Libs2") (part "RC06J_0R"))
    )
    (comp (ref "R43")
      (value "47K 5%")
      (footprint "RES0603")
      (description "47K,±5%,1/10W,0603,国巨,RC0603JR-0747KL")
      (fields (field (name "PART NUMBER") "101010103-0012"))
      (libsource (lib "Database_Libs2") (part "RC03J_47K"))
    )
    (comp (ref "R50")
      (value "0R 5%")
      (footprint "RES1206")
      (description "0Ω,±5%,1/4W,1206,国巨,RC1206JR-070RL")
      (fields (field (name "PART NUMBER") "101010101-0013"))
      (libsource (lib "Database_Libs2") (part "RC06J_0R"))
    )
    (comp (ref "R58")
      (value "1K 5%")
      (footprint "RES0603")
      (description "1K,±5%,1/10W,0603,国巨,RC0603JR-071KL")
      (fields (field (name "PART NUMBER") "101010103-0008"))
      (libsource (lib "Database_Libs2") (part "RC03J_1K"))
    )
    (comp (ref "R59")
      (value "10K 1%")
      (footprint "RES0603")
      (description "10K±1%,1/10W,0603")
      (fields (field (name "PART NUMBER") "101010103-0052"))
      (libsource (lib "Database_Libs2") (part "RC03J_10K"))
    )
    (comp (ref "R60")
      (value "1K 5%")
      (footprint "RES0603")
      (description "1K,±5%,1/10W,0603,国巨,RC0603JR-071KL")
      (fields (field (name "PART NUMBER") "101010103-0008"))
      (libsource (lib "Database_Libs2") (part "RC03J_1K"))
    )
    (comp (ref "R61")
      (value "10K 1%")
      (footprint "RES0603")
      (description "10K±1%,1/10W,0603")
      (fields (field (name "PART NUMBER") "101010103-0052"))
      (libsource (lib "Database_Libs2") (part "RC03J_10K"))
    )
    (comp (ref "R62")
      (value "1K 5%")
      (footprint "RES0603")
      (description "1K,±5%,1/10W,0603,国巨,RC0603JR-071KL")
      (fields (field (name "PART NUMBER") "101010103-0008"))
      (libsource (lib "Database_Libs2") (part "RC03J_1K"))
    )
    (comp (ref "R75")
      (value "3K 5%")
      (footprint "RES0603")
      (description "国巨,±5%,0603,,155 ℃,-55 ℃,RC0603JR-073KL,无铅,100 ppm/℃,1/10W,,3K")
      (fields (field (name "PART NUMBER") "101010103-0006"))
      (libsource (lib "Database_Libs2") (part "RC03J_3K"))
    )
    (comp (ref "R93")
      (value "10K 1%")
      (footprint "RES0603")
      (description "10K±1%,1/10W,0603")
      (fields (field (name "PART NUMBER") "101010103-0052"))
      (libsource (lib "Database_Libs2") (part "RC03J_10K"))
    )
    (comp (ref "R94")
      (value "10K 1%")
      (footprint "RES0603")
      (description "10K±1%,1/10W,0603")
      (fields (field (name "PART NUMBER") "101010103-0052"))
      (libsource (lib "Database_Libs2") (part "RC03J_10K"))
    )
    (comp (ref "R95")
      (value "100R 5%")
      (footprint "RES0603")
      (description "100R,±5%,1/10W,0603,国巨,RC0603JR-07100RL")
      (fields (field (name "PART NUMBER") "101010103-0022"))
      (libsource (lib "Database_Libs2") (part "RC03J_100R"))
    )
    (comp (ref "R96")
      (value "10K 5%")
      (footprint "RES0603")
      (description "国巨,±5%,0603,,155 ℃,-55 ℃,RC0603JR-071ML,无铅,200 ppm/℃,1/10W,,1M")
      (fields (field (name "PART NUMBER") "101010103-0002"))
      (libsource (lib "Database_Libs2") (part "RC03J_1M"))
    )
    (comp (ref "R97")
      (value "10K 5%")
      (footprint "RES0603")
      (description "国巨,±5%,0603,,155 ℃,-55 ℃,RC0603JR-071ML,无铅,200 ppm/℃,1/10W,,1M")
      (fields (field (name "PART NUMBER") "101010103-0002"))
      (libsource (lib "Database_Libs2") (part "RC03J_1M"))
    )
    (comp (ref "RXD")
      (value "TEST-PAD")
      (footprint "TEST-PAD")
      (description "单面焊盘测试点")
      (fields (field (name "PART NUMBER") "AD_WXHJ_TEST-PAD_01"))
      (libsource (lib "Database_Libs2") (part "TEST-PAD"))
    )
    (comp (ref "S1")
      (value "SWS_4_600_600_430")
      (footprint "SWS_4_600_600")
      (description "TS-1010GS-AR043,点触,6*6*4.3mm,贴片,东莞市讯普电子科技有限公司")
      (fields (field (name "PART NUMBER") "1011001-0062"))
      (libsource (lib "Database_Libs2") (part "07_SWS_4_600_600_430"))
    )
    (comp (ref "S2")
      (value "SWS_4_600_600_430")
      (footprint "SWS_4_600_600")
      (description "TS-1010GS-AR043,点触,6*6*4.3mm,贴片,东莞市讯普电子科技有限公司")
      (fields (field (name "PART NUMBER") "1011001-0062"))
      (libsource (lib "Database_Libs2") (part "07_SWS_4_600_600_430"))
    )
    (comp (ref "SCL")
      (value "TEST-PAD")
      (footprint "TEST-PAD")
      (description "单面焊盘测试点")
      (fields (field (name "PART NUMBER") "AD_WXHJ_TEST-PAD_01"))
      (libsource (lib "Database_Libs2") (part "TEST-PAD"))
    )
    (comp (ref "SDA")
      (value "TEST-PAD")
      (footprint "TEST-PAD")
      (description "单面焊盘测试点")
      (fields (field (name "PART NUMBER") "AD_WXHJ_TEST-PAD_01"))
      (libsource (lib "Database_Libs2") (part "TEST-PAD"))
    )
    (comp (ref "TVS1")
      (value "SMBJ6.0CA")
      (footprint "DO-214AA")
      (description "SMBJ6.0CA,DO-214AA,10.3 V,6.0 V,600 W,58.3 A,800 uA,上海君耀电子有限公司,SMBJ6.0CA")
      (fields (field (name "PART NUMBER") "101040101-0024"))
      (libsource (lib "Database_Libs2") (part "05_SMBJ6.0CA"))
    )
    (comp (ref "TVS2")
      (value "SMAJ5.0CA")
      (footprint "SMAJ5.0CA")
      (fields (field (name "BOM_SUPPLIER PART") "C693487") (field (name "CONTRIBUTOR") "LCSC"))
      (libsource (lib "Discrete_WX") (part "SMAJ5.0CA_C693487"))
    )
    (comp (ref "TXD")
      (value "TEST-PAD")
      (footprint "TEST-PAD")
      (description "单面焊盘测试点")
      (fields (field (name "PART NUMBER") "AD_WXHJ_TEST-PAD_01"))
      (libsource (lib "Database_Libs2") (part "TEST-PAD"))
    )
    (comp (ref "U1")
      (value "P25Q80H-SUH-IR")
      (footprint "SOP-8L-200MIL")
      (description "P25Q80H-SUH-IR,SOP8208mil,普冉半导体（上海）股份有限公司,P25Q80H-SUH-IR")
      (fields (field (name "PART NUMBER") "101050101-0218"))
      (libsource (lib "Database_Libs2") (part "04_P25Q80H-SUH-IR"))
    )
    (comp (ref "U2")
      (value "CE6232A50P")
      (footprint "SOT-89")
      (description "CE6232A50P,CE6232A50P,SOT89-3,8 V,1.8 V,0.11 V,5 V,500mA,0.8 uA,南京芯力微电子有限公司")
      (fields (field (name "PART NUMBER") "1010503-0028"))
      (libsource (lib "Database_Libs2") (part "02_CE6232A50P"))
    )
    (comp (ref "U3")
      (value "CE6232A33P")
      (footprint "SOT-89")
      (description "CE6232-3.3,CE6232-3.3,SOT89-3,8V,1.8V,0.11V,3.3V,300mA,0.8uA,南京芯力微电子有限公司")
      (fields (field (name "PART NUMBER") "1010503-0029"))
      (libsource (lib "Database_Libs2") (part "02_CE6232A33P"))
    )
    (comp (ref "U6")
      (value "CE6232A33P")
      (footprint "SOT-89")
      (description "CE6232-3.3,CE6232-3.3,SOT89-3,8V,1.8V,0.11V,3.3V,300mA,0.8uA,南京芯力微电子有限公司")
      (fields (field (name "PART NUMBER") "1010503-0029"))
      (libsource (lib "Database_Libs2") (part "02_CE6232A33P"))
    )
    (comp (ref "U7") (value "FM33LG0x8") (footprint "LQFP80") (libsource (lib "FM_MCU") (part "FM33LG0x8")))
    (comp (ref "U8")
      (value "DRV8837DSGR")
      (footprint "S-PWSON-N8")
      (description "DRV8837DSGR,S-PWSON-N8,TI,DRV8837DSGR")
      (fields (field (name "PART NUMBER") "101050101-0060"))
      (libsource (lib "Database_Libs2") (part "07_DRV8837DSGR"))
    )
    (comp (ref "U9")
      (value "ESAM")
      (footprint "SOP-8")
      (description "ESAM虚拟器件")
      (fields (field (name "PART NUMBER") "AD_XN_ESAM_01"))
      (libsource (lib "Database_Libs2") (part "04_ESAM"))
    )
    (comp (ref "U11")
      (value "IRM-3638J7")
      (footprint "IRM-3638J7")
      (description "IRM-3638J7  直脚,插件,6 V,6 V,亿光电子工业股份有限公司,IRM-3638J7")
      (fields (field (name "PART NUMBER") "101040101-0059"))
      (libsource (lib "Database_Libs2") (part "01_IRM-3638J7"))
    )
    (comp (ref "U20") (value "HP303B") (footprint "LGA_8") (libsource (lib "Schlib2") (part "HP303B")))
    (comp (ref "VIN1")
      (value "TEST-PAD")
      (footprint "TEST-PAD")
      (description "单面焊盘测试点")
      (fields (field (name "PART NUMBER") "AD_WXHJ_TEST-PAD_01"))
      (libsource (lib "Database_Libs2") (part "TEST-PAD"))
    )
    (comp (ref "VIN2")
      (value "TEST-PAD")
      (footprint "TEST-PAD")
      (description "单面焊盘测试点")
      (fields (field (name "PART NUMBER") "AD_WXHJ_TEST-PAD_01"))
      (libsource (lib "Database_Libs2") (part "TEST-PAD"))
    )
    (comp (ref "Y2")
      (value "SF32WK32768D71T005")
      (footprint "SMD-3215_2P")
      (description "SF32WK32768D71T005,3215,32.768kHz,-0.03 ppm/℃,无源,湖北泰晶电子科技股份有限公司,SF32WK32768D71T005")
      (fields (field (name "PART NUMBER") "1010601-0020"))
      (libsource (lib "Database_Libs2") (part "04_XTALSG7QD_32.768kD"))
    )
  )
  (nets
    (net (code "1") (name "/119") (class "Default")
      (node (ref "C59") (pin "1") (pinfunction "1_1") (pintype "passive"))
      (node (ref "C8") (pin "1") (pinfunction "1_1") (pintype "passive"))
      (node (ref "FB1") (pin "1") (pinfunction "1_1") (pintype "passive"))
      (node (ref "Q17") (pin "4") (pintype "passive"))
      (node (ref "U7") (pin "43") (pinfunction "PE5/SEG43/LPT32_CH4/CAN_TX_43") (pintype "passive"))
    )
    (net (code "2") (name "/BUZZ") (class "Default")
      (node (ref "R38") (pin "1") (pinfunction "1_1") (pintype "passive"))
      (node (ref "U7") (pin "57") (pinfunction "PC11/SEG20/U7816CLK/GPTO_CH3/ADC_IN16_57") (pintype "passive"))
    )
    (net (code "3") (name "/CLOSE") (class "Default")
      (node (ref "U7") (pin "19") (pinfunction "PD9(WKUP8)_19") (pintype "passive"))
      (node (ref "U8") (pin "5") (pinfunction "IN2_5") (pintype "passive"))
    )
    (net (code "4") (name "/COM0") (class "Default")
      (node (ref "LCD1") (pin "1") (pinfunction "COM0_1") (pintype "passive"))
      (node (ref "U7") (pin "6") (pinfunction "PA0/COM0/UART4_RX/ADC_IN5/LUT3_OUT_6") (pintype "passive"))
    )
    (net (code "5") (name "/COM1") (class "Default")
      (node (ref "LCD1") (pin "2") (pinfunction "COM1_2") (pintype "passive"))
      (node (ref "U7") (pin "7") (pinfunction "PA1/COM1/UART4_TX/ADC_IN12/LUT2_OUT_7") (pintype "passive"))
    )
    (net (code "6") (name "/COM2") (class "Default")
      (node (ref "LCD1") (pin "3") (pinfunction "COM2_3") (pintype "passive"))
      (node (ref "U7") (pin "8") (pinfunction "PA2/COM2/UART0_RX/LPUART0_RX_8") (pintype "passive"))
    )
    (net (code "7") (name "/COM3") (class "Default")
      (node (ref "LCD1") (pin "4") (pinfunction "COM3_4") (pintype "passive"))
      (node (ref "U7") (pin "9") (pinfunction "PA3/COM3/UART0_TX/LPUART0_TX_9") (pintype "passive"))
    )
    (net (code "8") (name "/COM4") (class "Default")
      (node (ref "LCD1") (pin "5") (pinfunction "COM4_5") (pintype "passive"))
      (node (ref "U7") (pin "10") (pinfunction "PA4/COM4/SEG28/GPT1_CH3/COMP2_INN1_10") (pintype "passive"))
    )
    (net (code "9") (name "/COM5") (class "Default")
      (node (ref "LCD1") (pin "6") (pinfunction "COM5_6") (pintype "passive"))
      (node (ref "U7") (pin "11") (pinfunction "PA5/COM5/SEG29/GPT1_CH4/COMP2_INN2_11") (pintype "passive"))
    )
    (net (code "10") (name "/COM6") (class "Default")
      (node (ref "LCD1") (pin "7") (pinfunction "COM6_7") (pintype "passive"))
      (node (ref "U7") (pin "12") (pinfunction "PA6/COM6/SEG30/OPA1_INN2/CAN_RX_12") (pintype "passive"))
    )
    (net (code "11") (name "/COM7") (class "Default")
      (node (ref "LCD1") (pin "8") (pinfunction "COM7_8") (pintype "passive"))
      (node (ref "U7") (pin "13") (pinfunction "PA7/COM7/SEG31/OPA1_INP2/CAN_TX_13") (pintype "passive"))
    )
    (net (code "12") (name "/Csb_Irda_En") (class "Default")
      (node (ref "R25") (pin "2") (pinfunction "2_2") (pintype "passive"))
      (node (ref "U7") (pin "58") (pinfunction "PC12/SEG21/U7816IO/GPTO_CH4/ADC_IN17_58") (pintype "passive"))
    )
    (net (code "13") (name "/Csb_Irda_Rx") (class "Default")
      (node (ref "C19") (pin "1") (pinfunction "1_1") (pintype "passive"))
      (node (ref "J9") (pin "3") (pinfunction "3_3") (pintype "passive"))
      (node (ref "Q7") (pin "3") (pinfunction "C_3") (pintype "passive"))
      (node (ref "R23") (pin "1") (pinfunction "1_1") (pintype "passive"))
      (node (ref "R31") (pin "2") (pinfunction "2_2") (pintype "passive"))
      (node (ref "U7") (pin "50") (pinfunction "PC4/SEG13/UART5_RX/COMP1_OUT/OPA1_OUT2_50") (pintype "passive"))
    )
    (net (code "14") (name "/Csb_Irda_Tx") (class "Default")
      (node (ref "J9") (pin "2") (pinfunction "2_2") (pintype "passive"))
      (node (ref "R16") (pin "1") (pinfunction "1_1") (pintype "passive"))
      (node (ref "R3") (pin "1") (pinfunction "1_1") (pintype "passive"))
      (node (ref "U7") (pin "51") (pinfunction "PC5/SEG14/UART5_TX/COMP2_OUT/DAC_OUT_51") (pintype "passive"))
    )
    (net (code "15") (name "/DW_CHEAK") (class "Default")
      (node (ref "C27") (pin "1") (pinfunction "1_1") (pintype "passive"))
      (node (ref "DW1") (pin "1") (pinfunction "1_1") (pintype "passive"))
      (node (ref "J2") (pin "3") (pinfunction "3_3") (pintype "passive"))
      (node (ref "U7") (pin "52") (pinfunction "PC6(WKUP4)/SEG15/COMP1_INN2/GPT1_ETR_52") (pintype "passive"))
    )
    (net (code "16") (name "/ESAM_CLK") (class "Default")
      (node (ref "U7") (pin "40") (pinfunction "PC13/SEG40/U7816CLK/LPT16_CH1_40") (pintype "passive"))
      (node (ref "U9") (pin "6") (pinfunction "CLK_6") (pintype "passive"))
    )
    (net (code "17") (name "/ESAM_POW") (class "Default")
      (node (ref "R20") (pin "1") (pinfunction "1_1") (pintype "passive"))
      (node (ref "U7") (pin "45") (pinfunction "PD12/VDISP1/SDA1/SPI2_MOSI_45") (pintype "passive"))
    )
    (net (code "18") (name "/ESAM_RST") (class "Default")
      (node (ref "U7") (pin "47") (pinfunction "PC1/VDISP3/GPT1_CH2/COMP3_INP2/LUT1_OUT_47") (pintype "passive"))
      (node (ref "U9") (pin "7") (pinfunction "RST_7") (pintype "passive"))
    )
    (net (code "19") (name "/ESAM_SDA") (class "Default")
      (node (ref "R22") (pin "2") (pinfunction "2_2") (pintype "passive"))
      (node (ref "U7") (pin "41") (pinfunction "PC14/SEG41/U7816IO/LPT16_CH2_41") (pintype "passive"))
      (node (ref "U9") (pin "3") (pinfunction "I/O_3") (pintype "passive"))
    )
    (net (code "20") (name "/FLASH_CLK") (class "Default")
      (node (ref "U1") (pin "6") (pinfunction "SCK_6") (pintype "passive"))
      (node (ref "U7") (pin "37") (pinfunction "PE1/SEG37/SPI0_SCK_37") (pintype "passive"))
    )
    (net (code "21") (name "/FLASH_CS") (class "Default")
      (node (ref "U1") (pin "1") (pinfunction "CE#_1") (pintype "passive"))
      (node (ref "U7") (pin "44") (pinfunction "PB15/VDISP0/SCL1/SPI2_MISO_44") (pintype "passive"))
    )
    (net (code "22") (name "/FLASH_CTL") (class "Default")
      (node (ref "R12") (pin "1") (pinfunction "1_1") (pintype "passive"))
      (node (ref "U7") (pin "46") (pinfunction "PC0/VDISP2/GPT1_CH1/COMP3_INP1/LUT0_OUT_46") (pintype "passive"))
    )
    (net (code "23") (name "/FLASH_MISO") (class "Default")
      (node (ref "U1") (pin "2") (pinfunction "SO_2") (pintype "passive"))
      (node (ref "U7") (pin "38") (pinfunction "PE2/SEG38/SPI0_MISO_38") (pintype "passive"))
    )
    (net (code "24") (name "/FLASH_MOSI") (class "Default")
      (node (ref "U1") (pin "5") (pinfunction "SI_5") (pintype "passive"))
      (node (ref "U7") (pin "39") (pinfunction "PE3/SEG39/SPI0_MOSI_39") (pintype "passive"))
    )
    (net (code "25") (name "/GPRS_POWER") (class "Default")
      (node (ref "R40") (pin "1") (pinfunction "1_1") (pintype "passive"))
      (node (ref "U7") (pin "76") (pinfunction "PD5/SEG27/SPI1_MOSI/ADC_IN3/LPT16_ETR_76") (pintype "passive"))
    )
    (net (code "26") (name "/GPRS_RST") (class "Default")
      (node (ref "U7") (pin "77") (pinfunction "PD6(WKUP7)/ATIM_BRK2/ADC_1N10/ANATST_77") (pintype "passive"))
    )
    (net (code "27") (name "/GPRS_WAKEUP") (class "Default")
      (node (ref "U7") (pin "69") (pinfunction "PE7/COMP3_OUT_69") (pintype "passive"))
    )
    (net (code "28") (name "/HALL1_INTP6") (class "Default")
      (node (ref "U7") (pin "33") (pinfunction "PB12(WKUP3)/ATIM_ETR/FOUT1/OPA1_OUT1_33") (pintype "passive"))
    )
    (net (code "29") (name "/HIC1_EXT") (class "Default")
      (node (ref "J3") (pin "3") (pinfunction "3_3") (pintype "passive"))
      (node (ref "U7") (pin "68") (pinfunction "PE6(WKUP9)_68") (pintype "passive"))
    )
    (net (code "30") (name "/IN1") (class "Default")
      (node (ref "119") (pin "1") (pinfunction "1_1") (pintype "passive"))
      (node (ref "D10") (pin "3") (pinfunction "C_3") (pintype "passive"))
      (node (ref "P5") (pin "1") (pinfunction "1_1") (pintype "passive"))
      (node (ref "R75") (pin "1") (pinfunction "1_1") (pintype "passive"))
      (node (ref "TVS2") (pin "1") (pinfunction "1_1") (pintype "passive"))
    )
    (net (code "31") (name "/IN2") (class "Default")
      (node (ref "D13") (pin "1") (pinfunction "1_1") (pintype "passive"))
      (node (ref "FB2") (pin "2") (pinfunction "2_2") (pintype "passive"))
      (node (ref "P5") (pin "2") (pinfunction "2_2") (pintype "passive"))
      (node (ref "Q17") (pin "2") (pintype "passive"))
    )
    (net (code "32") (name "/INTP1") (class "Default")
      (node (ref "C47") (pin "2") (pinfunction "2_2") (pintype "passive"))
      (node (ref "S1") (pin "1") (pinfunction "1_1") (pintype "passive"))
      (node (ref "U7") (pin "20") (pinfunction "PE8_20") (pintype "passive"))
    )
    (net (code "33") (name "/INTP4") (class "Default")
      (node (ref "C46") (pin "2") (pinfunction "2_2") (pintype "passive"))
      (node (ref "S2") (pin "1") (pinfunction "1_1") (pintype "passive"))
      (node (ref "U7") (pin "14") (pinfunction "PA8/SEG0/LPT32_CH1/COMP2_INP1/SPI1_SSN_14") (pintype "passive"))
    )
    (net (code "34") (name "/IRED_RXD_EN") (class "Default")
      (node (ref "D6") (pin "2") (pinfunction "2_2") (pintype "passive"))
      (node (ref "R23") (pin "2") (pinfunction "2_2") (pintype "passive"))
      (node (ref "R32") (pin "1") (pinfunction "1_1") (pintype "passive"))
      (node (ref "R34") (pin "1") (pinfunction "1_1") (pintype "passive"))
      (node (ref "U7") (pin "59") (pinfunction "PH15/RTCOUT/TAMPER_59") (pintype "passive"))
    )
    (net (code "35") (name "/LED") (class "Default")
      (node (ref "R37") (pin "1") (pinfunction "1_1") (pintype "passive"))
      (node (ref "U7") (pin "54") (pinfunction "PC8/SEG17/ADC_IN13/SPI2_SCK_54") (pintype "passive"))
    )
    (net (code "36") (name "/MCU_RxD1") (class "Default")
      (node (ref "U7") (pin "23") (pinfunction "PB2(WKUP2)/VCIN1/UART4_RX/ATIM_CHIN_23") (pintype "passive"))
    )
    (net (code "37") (name "/MCU_TxD1") (class "Default")
      (node (ref "U7") (pin "24") (pinfunction "PB3/VCIN2/UART4_TX/ATIM_CH2N_24") (pintype "passive"))
    )
    (net (code "38") (name "/MOTO_B") (class "Default")
      (node (ref "C37") (pin "2") (pinfunction "2_2") (pintype "passive"))
      (node (ref "C60") (pin "2") (pinfunction "2_2") (pintype "passive"))
      (node (ref "J2") (pin "1") (pinfunction "1_1") (pintype "passive"))
      (node (ref "M_B") (pin "1") (pinfunction "1_1") (pintype "passive"))
      (node (ref "P2") (pin "1") (pinfunction "1_1") (pintype "passive"))
      (node (ref "TVS1") (pin "2") (pinfunction "2_2") (pintype "passive"))
      (node (ref "U8") (pin "3") (pinfunction "OUT2_3") (pintype "passive"))
    )
    (net (code "39") (name "/MOTO_R") (class "Default")
      (node (ref "C37") (pin "1") (pinfunction "1_1") (pintype "passive"))
      (node (ref "C60") (pin "1") (pinfunction "1_1") (pintype "passive"))
      (node (ref "J2") (pin "2") (pinfunction "2_2") (pintype "passive"))
      (node (ref "M_R") (pin "1") (pinfunction "1_1") (pintype "passive"))
      (node (ref "P2") (pin "2") (pinfunction "2_2") (pintype "passive"))
      (node (ref "TVS1") (pin "1") (pinfunction "1_1") (pintype "passive"))
      (node (ref "U8") (pin "2") (pinfunction "OUT1_2") (pintype "passive"))
    )
    (net (code "40") (name "/NB_POWER") (class "Default")
      (node (ref "Q20") (pin "3") (pinfunction "C_3") (pintype "passive"))
      (node (ref "R18") (pin "1") (pinfunction "1_1") (pintype "passive"))
    )
    (net (code "41") (name "/OPEN") (class "Default")
      (node (ref "U7") (pin "71") (pinfunction "PD0/SEG22/UART5_RX/ADC_IN7/GPT2_CH1_71") (pintype "passive"))
      (node (ref "U8") (pin "6") (pinfunction "IN1_6") (pintype "passive"))
    )
    (net (code "42") (name "/RST") (class "Default")
      (node (ref "C49") (pin "2") (pinfunction "2_2") (pintype "passive"))
      (node (ref "R95") (pin "1") (pinfunction "1_1") (pintype "passive"))
      (node (ref "U7") (pin "80") (pinfunction "NRST_80") (pintype "passive"))
    )
    (net (code "43") (name "/RXD0") (class "Default")
      (node (ref "U7") (pin "3") (pinfunction "PA13/UART0_RX/LPUART0_RX/ADC_IN4_3") (pintype "passive"))
    )
    (net (code "44") (name "/S0") (class "Default")
      (node (ref "LCD1") (pin "9") (pinfunction "SEG0_9") (pintype "passive"))
      (node (ref "U7") (pin "36") (pinfunction "PE0/SEG36/SPI0_SSN_36") (pintype "passive"))
    )
    (net (code "45") (name "/S1") (class "Default")
      (node (ref "LCD1") (pin "10") (pinfunction "SEG1_10") (pintype "passive"))
      (node (ref "U7") (pin "35") (pinfunction "PB14/SEG12/UART1_TX/LPUART1_TX_35") (pintype "passive"))
    )
    (net (code "46") (name "/S2") (class "Default")
      (node (ref "LCD1") (pin "11") (pinfunction "SEG2_11") (pintype "passive"))
      (node (ref "U7") (pin "32") (pinfunction "PB11/SEG10/SPI0_MOSI/GPT0_CH2/OPA1_INP1_32") (pintype "passive"))
    )
    (net (code "47") (name "/S3") (class "Default")
      (node (ref "LCD1") (pin "12") (pinfunction "SEG3_12") (pintype "passive"))
      (node (ref "U7") (pin "31") (pinfunction "PB10/SEG9/SPI0_MISO/GPT0_CH1/OPA1_INN1_31") (pintype "passive"))
    )
    (net (code "48") (name "/S4") (class "Default")
      (node (ref "LCD1") (pin "13") (pinfunction "SEG4_13") (pintype "passive"))
      (node (ref "U7") (pin "30") (pinfunction "PB9/SEG8/SPI0_SCK/GPT0_ETR/COMP1_INP2_30") (pintype "passive"))
    )
    (net (code "49") (name "/S5") (class "Default")
      (node (ref "LCD1") (pin "14") (pinfunction "SEG5_14") (pintype "passive"))
      (node (ref "U7") (pin "29") (pinfunction "PB8/SEG7/SPI0_SSN/ATIM_CH3N/COMP1_INP1_29") (pintype "passive"))
    )
    (net (code "50") (name "/S6") (class "Default")
      (node (ref "LCD1") (pin "15") (pinfunction "SEG6_15") (pintype "passive"))
      (node (ref "U7") (pin "28") (pinfunction "PB7/SEG6/ATIM_CH4/SPI2_SCK/ANATST_28") (pintype "passive"))
    )
    (net (code "51") (name "/S7") (class "Default")
      (node (ref "LCD1") (pin "16") (pinfunction "SEG7_16") (pintype "passive"))
      (node (ref "U7") (pin "27") (pinfunction "PB6/SEG5/ATIM_CH3/SPI2_SSN_27") (pintype "passive"))
    )
    (net (code "52") (name "/S8") (class "Default")
      (node (ref "LCD1") (pin "17") (pinfunction "SEG8_17") (pintype "passive"))
      (node (ref "U7") (pin "26") (pinfunction "PB5/SEG4/ATIM_CH2/LPUART2_TX/COMP3_INN2_26") (pintype "passive"))
    )
    (net (code "53") (name "/S9") (class "Default")
      (node (ref "LCD1") (pin "18") (pinfunction "SEG9_18") (pintype "passive"))
      (node (ref "U7") (pin "25") (pinfunction "PB4/SEG3/ATIM_CH1/LPUART2_RX/COMP3_INN1_25") (pintype "passive"))
    )
    (net (code "54") (name "/S10") (class "Default")
      (node (ref "LCD1") (pin "19") (pinfunction "SEG10_19") (pintype "passive"))
      (node (ref "U7") (pin "22") (pinfunction "PB1/SEG35/UART3_TX/SPI1_MOSI/OPA1_OUT4_22") (pintype "passive"))
    )
    (net (code "55") (name "/S11") (class "Default")
      (node (ref "LCD1") (pin "20") (pinfunction "SEG11_20") (pintype "passive"))
      (node (ref "U7") (pin "21") (pinfunction "PB0/SEG34/UART3_RX/SPI1_MISO/OPA1_OUT3_21") (pintype "passive"))
    )
    (net (code "56") (name "/S12") (class "Default")
      (node (ref "LCD1") (pin "21") (pinfunction "SEG12_21") (pintype "passive"))
      (node (ref "U7") (pin "18") (pinfunction "PA12/SEG33/SDA0/LPUART2_TX_18") (pintype "passive"))
    )
    (net (code "57") (name "/S13") (class "Default")
      (node (ref "LCD1") (pin "22") (pinfunction "SEG13_22") (pintype "passive"))
      (node (ref "U7") (pin "17") (pinfunction "PA11/SEG32/SCL0/LPUART2_RX_17") (pintype "passive"))
    )
    (net (code "58") (name "/S14") (class "Default")
      (node (ref "LCD1") (pin "23") (pinfunction "SEG14_23") (pintype "passive"))
      (node (ref "U7") (pin "16") (pinfunction "PA10/WKUP1/SEG2/LPT32_ETR/COMP1_INN1_16") (pintype "passive"))
    )
    (net (code "59") (name "/S15") (class "Default")
      (node (ref "LCD1") (pin "24") (pinfunction "SEG15_24") (pintype "passive"))
      (node (ref "U7") (pin "15") (pinfunction "PA9/SEG1/LPT32_CH2/COMP2_INP2/SPI1_SCK_15") (pintype "passive"))
    )
    (net (code "60") (name "/S16") (class "Default")
      (node (ref "LCD1") (pin "25") (pinfunction "SEG16_25") (pintype "passive"))
      (node (ref "U7") (pin "73") (pinfunction "PD2/SEG24/SPI1_SSN/ADC_IN8/GPT2_CH3_73") (pintype "passive"))
    )
    (net (code "61") (name "/S17") (class "Default")
      (node (ref "LCD1") (pin "26") (pinfunction "SEG17_26") (pintype "passive"))
      (node (ref "U7") (pin "74") (pinfunction "PD3/SEG25/SPI1_SCK/ADC_IN2/GPT2_CH4_74") (pintype "passive"))
    )
    (net (code "62") (name "/SLEEP") (class "Default")
      (node (ref "U7") (pin "72") (pinfunction "PD1/SEG23/UART5_TX/ADC_IN1/GPT2_CH2_72") (pintype "passive"))
      (node (ref "U8") (pin "7") (pinfunction "~{SLEEP}_7") (pintype "passive"))
    )
    (net (code "63") (name "/SWCLK") (class "Default")
      (node (ref "J8") (pin "2") (pinfunction "2_2") (pintype "passive"))
      (node (ref "R94") (pin "1") (pinfunction "1_1") (pintype "passive"))
      (node (ref "U7") (pin "78") (pinfunction "PD7/UART3_RX/SWCLK_78") (pintype "passive"))
    )
    (net (code "64") (name "/SWIO") (class "Default")
      (node (ref "J8") (pin "3") (pinfunction "3_3") (pintype "passive"))
      (node (ref "R93") (pin "2") (pinfunction "2_2") (pintype "passive"))
      (node (ref "U7") (pin "79") (pinfunction "PD8/UART3_TX/SWIO_79") (pintype "passive"))
    )
    (net (code "65") (name "/TXD0") (class "Default")
      (node (ref "U7") (pin "4") (pinfunction "PA14/UART0_TX/LPUART0_TX/ADC_IN11_4") (pintype "passive"))
    )
    (net (code "66") (name "/UMCU TXD1 INT") (class "Default")
      (node (ref "C16") (pin "1") (pinfunction "1_1") (pintype "passive"))
      (node (ref "R4") (pin "2") (pinfunction "2_2") (pintype "passive"))
      (node (ref "U7") (pin "42") (pinfunction "PC15/SEG42/LPT32_CH3/CAN_RX_42") (pintype "passive"))
    )
    (net (code "67") (name "/UMCU_RXD1") (class "Default")
      (node (ref "R4") (pin "1") (pinfunction "1_1") (pintype "passive"))
      (node (ref "R58") (pin "1") (pinfunction "1_1") (pintype "passive"))
      (node (ref "R62") (pin "1") (pinfunction "1_1") (pintype "passive"))
      (node (ref "U7") (pin "48") (pinfunction "PC2/XTHIN/UART1_RX/LPUART1_RX_48") (pintype "passive"))
    )
    (net (code "68") (name "/UMCU_TXD1") (class "Default")
      (node (ref "R60") (pin "1") (pinfunction "1_1") (pintype "passive"))
      (node (ref "U7") (pin "49") (pinfunction "PC3/XTHOUT/UART1_TX/LPUART1_TX_49") (pintype "passive"))
    )
    (net (code "69") (name "/UMU_RXD") (class "Default")
      (node (ref "J3") (pin "4") (pinfunction "4_4") (pintype "passive"))
      (node (ref "R60") (pin "2") (pinfunction "2_2") (pintype "passive"))
      (node (ref "RXD") (pin "1") (pinfunction "1_1") (pintype "passive"))
    )
    (net (code "70") (name "/UMU_TXD") (class "Default")
      (node (ref "J3") (pin "2") (pinfunction "2_2") (pintype "passive"))
      (node (ref "R61") (pin "2") (pinfunction "2_2") (pintype "passive"))
      (node (ref "R62") (pin "2") (pinfunction "2_2") (pintype "passive"))
      (node (ref "TXD") (pin "1") (pinfunction "1_1") (pintype "passive"))
    )
    (net (code "71") (name "/VDD_BLE_CTL") (class "Default")
      (node (ref "U7") (pin "75") (pinfunction "PD4/SEG26/SPI1_MISO/ADC_IN9/GPT2_ETR_75") (pintype "passive"))
    )
    (net (code "72") (name "/VIN_CHEAK") (class "Default")
      (node (ref "C40") (pin "2") (pinfunction "2_2") (pintype "passive"))
      (node (ref "R13") (pin "1") (pinfunction "1_1") (pintype "passive"))
      (node (ref "R9") (pin "2") (pinfunction "2_2") (pintype "passive"))
      (node (ref "U7") (pin "53") (pinfunction "PC7/SEG16/ADC_IN6/SPI2_SSN_53") (pintype "passive"))
    )
    (net (code "73") (name "/VIN_CHEAK_EN") (class "Default")
      (node (ref "R14") (pin "1") (pinfunction "1_1") (pintype "passive"))
      (node (ref "U7") (pin "56") (pinfunction "PC10(WKUP5)/SEG19/ADC_IN15/SPI2_MOSI_56") (pintype "passive"))
    )
    (net (code "74") (name "/VNB_CHEAK") (class "Default")
      (node (ref "C34") (pin "2") (pinfunction "2_2") (pintype "passive"))
      (node (ref "R24") (pin "2") (pinfunction "2_2") (pintype "passive"))
      (node (ref "R35") (pin "1") (pinfunction "1_1") (pintype "passive"))
      (node (ref "U7") (pin "70") (pinfunction "PD11(WKUP6)/FOUT0/ADC_IN0/ATIM_BRK1_70") (pintype "passive"))
    )
    (net (code "75") (name "/VNB_CHEAK_EN") (class "Default")
      (node (ref "R36") (pin "1") (pinfunction "1_1") (pintype "passive"))
      (node (ref "U7") (pin "55") (pinfunction "PC9/SEG18/ADC_IN14/SPI2_MISO_55") (pintype "passive"))
    )
    (net (code "76") (name "/WY_POW") (class "Default")
      (node (ref "C10") (pin "1") (pinfunction "1_1") (pintype "passive"))
      (node (ref "C64") (pin "1") (pinfunction "1_1") (pintype "passive"))
      (node (ref "J1") (pin "4") (pinfunction "4_4") (pintype "passive"))
      (node (ref "POW") (pin "1") (pinfunction "1_1") (pintype "passive"))
      (node (ref "R29") (pin "1") (pinfunction "1_1") (pintype "passive"))
      (node (ref "R30") (pin "1") (pinfunction "1_1") (pintype "passive"))
      (node (ref "R97") (pin "2") (pinfunction "2_2") (pintype "passive"))
      (node (ref "U20") (pin "1") (pinfunction "VDDIO_1") (pintype "passive"))
      (node (ref "U20") (pin "3") (pinfunction "VDD_3") (pintype "passive"))
      (node (ref "U7") (pin "5") (pinfunction "PA15/WKUP0/SVS/COMP3_OUT_5") (pintype "passive"))
    )
    (net (code "77") (name "/WY_SCL") (class "Default")
      (node (ref "C39") (pin "2") (pinfunction "2_2") (pintype "passive"))
      (node (ref "J1") (pin "2") (pinfunction "2_2") (pintype "passive"))
      (node (ref "R29") (pin "2") (pinfunction "2_2") (pintype "passive"))
      (node (ref "SCL") (pin "1") (pinfunction "1_1") (pintype "passive"))
      (node (ref "U20") (pin "5") (pinfunction "SCL_5") (pintype "passive"))
      (node (ref "U7") (pin "2") (pinfunction "PE9/CAN_TX/ADC_IN19_2") (pintype "passive"))
    )
    (net (code "78") (name "/WY_SDA") (class "Default")
      (node (ref "C45") (pin "1") (pinfunction "1_1") (pintype "passive"))
      (node (ref "J1") (pin "3") (pinfunction "3_3") (pintype "passive"))
      (node (ref "R30") (pin "2") (pinfunction "2_2") (pintype "passive"))
      (node (ref "SDA") (pin "1") (pinfunction "1_1") (pintype "passive"))
      (node (ref "U20") (pin "6") (pinfunction "SDA_6") (pintype "passive"))
      (node (ref "U7") (pin "1") (pinfunction "PD10/CAN_RX/ADC_IN18_1") (pintype "passive"))
    )
    (net (code "79") (name "/X1") (class "Default")
      (node (ref "U7") (pin "34") (pinfunction "PB13/SEG11/UART1_RX/LPUART1_RX_34") (pintype "passive"))
    )
    (net (code "80") (name "/XT1") (class "Default")
      (node (ref "C28") (pin "2") (pinfunction "2_2") (pintype "passive"))
      (node (ref "U7") (pin "61") (pinfunction "XT32KI_61") (pintype "passive"))
      (node (ref "Y2") (pin "1") (pinfunction "1_1") (pintype "passive"))
    )
    (net (code "81") (name "/XT2") (class "Default")
      (node (ref "C7") (pin "2") (pinfunction "2_2") (pintype "passive"))
      (node (ref "U7") (pin "60") (pinfunction "XT32KO_60") (pintype "passive"))
      (node (ref "Y2") (pin "2") (pinfunction "2_2") (pintype "passive"))
    )
    (net (code "82") (name "3.6V") (class "Default")
      (node (ref "3.6V") (pin "1") (pinfunction "1_1") (pintype "passive"))
      (node (ref "C14") (pin "1") (pinfunction "1_1") (pintype "passive"))
      (node (ref "C63") (pin "1") (pinfunction "1_1") (pintype "passive"))
      (node (ref "C9") (pin "1") (pinfunction "1_1") (pintype "passive"))
      (node (ref "D3") (pin "2") (pinfunction "2_2") (pintype "passive"))
      (node (ref "D7") (pin "3") (pinfunction "C_3") (pintype "passive"))
      (node (ref "U3") (pin "2") (pinfunction "Vin_2") (pintype "passive"))
    )
    (net (code "83") (name "5V") (class "Default")
      (node (ref "5V") (pin "1") (pinfunction "1_1") (pintype "passive"))
      (node (ref "C12") (pin "1") (pinfunction "1_1") (pintype "passive"))
      (node (ref "C35") (pin "1") (pinfunction "1_1") (pintype "passive"))
      (node (ref "D3") (pin "1") (pinfunction "1_1") (pintype "passive"))
      (node (ref "D8") (pin "1") (pinfunction "1_1") (pintype "passive"))
      (node (ref "R42") (pin "2") (pinfunction "2_2") (pintype "passive"))
      (node (ref "U2") (pin "3") (pinfunction "Vout_3") (pintype "passive"))
      (node (ref "U8") (pin "1") (pinfunction "VM_1") (pintype "passive"))
    )
    (net (code "84") (name "GND") (class "Default")
      (node (ref "C10") (pin "2") (pinfunction "2_2") (pintype "passive"))
      (node (ref "C11") (pin "2") (pinfunction "2_2") (pintype "passive"))
      (node (ref "C13") (pin "1") (pinfunction "1_1") (pintype "passive"))
      (node (ref "C14") (pin "2") (pinfunction "2_2") (pintype "passive"))
      (node (ref "C15") (pin "2") (pinfunction "2_2") (pintype "passive"))
      (node (ref "C16") (pin "2") (pinfunction "2_2") (pintype "passive"))
      (node (ref "C17") (pin "2") (pinfunction "2_2") (pintype "passive"))
      (node (ref "C18") (pin "2") (pinfunction "2_2") (pintype "passive"))
      (node (ref "C19") (pin "2") (pinfunction "2_2") (pintype "passive"))
      (node (ref "C20") (pin "2") (pinfunction "2_2") (pintype "passive"))
      (node (ref "C21") (pin "2") (pinfunction "2_2") (pintype "passive"))
      (node (ref "C23") (pin "2") (pinfunction "2_2") (pintype "passive"))
      (node (ref "C27") (pin "2") (pinfunction "2_2") (pintype "passive"))
      (node (ref "C28") (pin "1") (pinfunction "1_1") (pintype "passive"))
      (node (ref "C29") (pin "1") (pinfunction "1_1") (pintype "passive"))
      (node (ref "C3") (pin "2") (pinfunction "2_2") (pintype "passive"))
      (node (ref "C30") (pin "2") (pinfunction "2_2") (pintype "passive"))
      (node (ref "C31") (pin "2") (pinfunction "2_2") (pintype "passive"))
      (node (ref "C34") (pin "1") (pinfunction "1_1") (pintype "passive"))
      (node (ref "C35") (pin "2") (pinfunction "2_2") (pintype "passive"))
      (node (ref "C36") (pin "2") (pinfunction "2_2") (pintype "passive"))
      (node (ref "C38") (pin "2") (pinfunction "2_2") (pintype "passive"))
      (node (ref "C39") (pin "1") (pinfunction "1_1") (pintype "passive"))
      (node (ref "C4") (pin "2") (pinfunction "2_2") (pintype "passive"))
      (node (ref "C40") (pin "1") (pinfunction "1_1") (pintype "passive"))
      (node (ref "C42") (pin "2") (pinfunction "2_2") (pintype "passive"))
      (node (ref "C44") (pin "1") (pinfunction "1_1") (pintype "passive"))
      (node (ref "C45") (pin "2") (pinfunction "2_2") (pintype "passive"))
      (node (ref "C46") (pin "1") (pinfunction "1_1") (pintype "passive"))
      (node (ref "C47") (pin "1") (pinfunction "1_1") (pintype "passive"))
      (node (ref "C48") (pin "1") (pinfunction "1_1") (pintype "passive"))
      (node (ref "C49") (pin "1") (pinfunction "1_1") (pintype "passive"))
      (node (ref "C5") (pin "2") (pinfunction "2_2") (pintype "passive"))
      (node (ref "C50") (pin "2") (pinfunction "2_2") (pintype "passive"))
      (node (ref "C51") (pin "2") (pinfunction "2_2") (pintype "passive"))
      (node (ref "C53") (pin "2") (pinfunction "2_2") (pintype "passive"))
      (node (ref "C57") (pin "2") (pinfunction "2_2") (pintype "passive"))
      (node (ref "C58") (pin "2") (pinfunction "2_2") (pintype "passive"))
      (node (ref "C59") (pin "2") (pinfunction "2_2") (pintype "passive"))
      (node (ref "C6") (pin "2") (pinfunction "2_2") (pintype "passive"))
      (node (ref "C63") (pin "2") (pinfunction "2_2") (pintype "passive"))
      (node (ref "C64") (pin "2") (pinfunction "2_2") (pintype "passive"))
      (node (ref "C65") (pin "1") (pinfunction "1_1") (pintype "passive"))
      (node (ref "C7") (pin "1") (pinfunction "1_1") (pintype "passive"))
      (node (ref "C8") (pin "2") (pinfunction "2_2") (pintype "passive"))
      (node (ref "C9") (pin "2") (pinfunction "2_2") (pintype "passive"))
      (node (ref "FB2") (pin "1") (pinfunction "1_1") (pintype "passive"))
      (node (ref "J1") (pin "1") (pinfunction "1_1") (pintype "passive"))
      (node (ref "J2") (pin "4") (pinfunction "4_4") (pintype "passive"))
      (node (ref "J3") (pin "1") (pinfunction "1_1") (pintype "passive"))
      (node (ref "J4") (pin "2") (pinfunction "2_2") (pintype "passive"))
      (node (ref "J4") (pin "3") (pinfunction "3_3") (pintype "passive"))
      (node (ref "J4") (pin "4") (pinfunction "4_4") (pintype "passive"))
      (node (ref "J7") (pin "2") (pinfunction "2_2") (pintype "passive"))
      (node (ref "J7") (pin "3") (pinfunction "3_3") (pintype "passive"))
      (node (ref "J7") (pin "4") (pinfunction "4_4") (pintype "passive"))
      (node (ref "J8") (pin "4") (pinfunction "4_4") (pintype "passive"))
      (node (ref "J9") (pin "1") (pinfunction "1_1") (pintype "passive"))
      (node (ref "P2") (pin "3") (pinfunction "3_3") (pintype "passive"))
      (node (ref "P2") (pin "4") (pinfunction "4_4") (pintype "passive"))
      (node (ref "P5") (pin "3") (pinfunction "3_3") (pintype "passive"))
      (node (ref "P5") (pin "4") (pinfunction "4_4") (pintype "passive"))
      (node (ref "Q11") (pin "2") (pinfunction "E_2") (pintype "passive"))
      (node (ref "Q14") (pin "2") (pinfunction "E_2") (pintype "passive"))
      (node (ref "Q17") (pin "3") (pintype "passive"))
      (node (ref "Q20") (pin "2") (pinfunction "E_2") (pintype "passive"))
      (node (ref "Q22") (pin "3") (pinfunction "C_3") (pintype "passive"))
      (node (ref "Q3") (pin "2") (pinfunction "E_2") (pintype "passive"))
      (node (ref "Q7") (pin "2") (pinfunction "E_2") (pintype "passive"))
      (node (ref "Q9") (pin "3") (pinfunction "C_3") (pintype "passive"))
      (node (ref "R13") (pin "2") (pinfunction "2_2") (pintype "passive"))
      (node (ref "R35") (pin "2") (pinfunction "2_2") (pintype "passive"))
      (node (ref "R43") (pin "1") (pinfunction "1_1") (pintype "passive"))
      (node (ref "R5") (pin "1") (pinfunction "1_1") (pintype "passive"))
      (node (ref "R96") (pin "2") (pinfunction "2_2") (pintype "passive"))
      (node (ref "S1") (pin "2") (pinfunction "2_2") (pintype "passive"))
      (node (ref "S2") (pin "2") (pinfunction "2_2") (pintype "passive"))
      (node (ref "TVS2") (pin "2") (pinfunction "2_2") (pintype "passive"))
      (node (ref "U1") (pin "4") (pinfunction "VSS_4") (pintype "passive"))
      (node (ref "U11") (pin "2") (pinfunction "GND_2") (pintype "passive"))
      (node (ref "U2") (pin "1") (pinfunction "GND_1") (pintype "passive"))
      (node (ref "U20") (pin "2") (pinfunction "GND_2") (pintype "passive"))
      (node (ref "U3") (pin "1") (pinfunction "GND_1") (pintype "passive"))
      (node (ref "U6") (pin "1") (pinfunction "GND_1") (pintype "passive"))
      (node (ref "U7") (pin "63") (pinfunction "VSS(VSSA)_63") (pintype "passive"))
      (node (ref "U7") (pin "65") (pinfunction "VREFN_65") (pintype "passive"))
      (node (ref "U8") (pin "4") (pinfunction "GND_4") (pintype "passive"))
      (node (ref "U8") (pin "9") (pinfunction "Pad_9") (pintype "passive"))
      (node (ref "U9") (pin "1") (pinfunction "GND_1") (pintype "passive"))
    )
    (net (code "85") (name "GPRS_3.6V") (class "Default")
      (node (ref "C20") (pin "1") (pinfunction "1_1") (pintype "passive"))
      (node (ref "C3") (pin "1") (pinfunction "1_1") (pintype "passive"))
      (node (ref "C42") (pin "1") (pinfunction "1_1") (pintype "passive"))
      (node (ref "C51") (pin "1") (pinfunction "1_1") (pintype "passive"))
      (node (ref "C53") (pin "1") (pinfunction "1_1") (pintype "passive"))
      (node (ref "Q15") (pin "3") (pinfunction "D_3") (pintype "passive"))
    )
    (net (code "86") (name "Net-(B1-+)") (class "Default")
      (node (ref "B1") (pin "1") (pinfunction "+_1") (pintype "passive"))
      (node (ref "R27") (pin "1") (pinfunction "1_1") (pintype "passive"))
    )
    (net (code "87") (name "Net-(B1--)") (class "Default")
      (node (ref "B1") (pin "2") (pinfunction "-_2") (pintype "passive"))
      (node (ref "Q11") (pin "3") (pinfunction "C_3") (pintype "passive"))
    )
    (net (code "88") (name "Net-(C12-Pad2)") (class "Default")
      (node (ref "C12") (pin "2") (pinfunction "2_2") (pintype "passive"))
      (node (ref "C50") (pin "1") (pinfunction "1_1") (pintype "passive"))
    )
    (net (code "89") (name "Net-(D1-Pad2)") (class "Default")
      (node (ref "D1") (pin "2") (pinfunction "2_2") (pintype "passive"))
      (node (ref "R37") (pin "2") (pinfunction "2_2") (pintype "passive"))
    )
    (net (code "90") (name "Net-(D5-Pad2)") (class "Default")
      (node (ref "D5") (pin "2") (pinfunction "2_2") (pintype "passive"))
      (node (ref "R15") (pin "2") (pinfunction "2_2") (pintype "passive"))
    )
    (net (code "91") (name "Net-(D6-Pad1)") (class "Default")
      (node (ref "D6") (pin "1") (pinfunction "1_1") (pintype "passive"))
      (node (ref "R19") (pin "2") (pinfunction "2_2") (pintype "passive"))
    )
    (net (code "92") (name "Net-(D10-A-Pad1)") (class "Default")
      (node (ref "D10") (pin "1") (pinfunction "A_1") (pintype "passive"))
      (node (ref "D10") (pin "2") (pinfunction "A_2") (pintype "passive"))
      (node (ref "FB1") (pin "2") (pinfunction "2_2") (pintype "passive"))
    )
    (net (code "93") (name "Net-(D13-Pad2)") (class "Default")
      (node (ref "D13") (pin "2") (pinfunction "2_2") (pintype "passive"))
      (node (ref "Q17") (pin "1") (pintype "passive"))
      (node (ref "R75") (pin "2") (pinfunction "2_2") (pintype "passive"))
    )
    (net (code "94") (name "Net-(J8-Pad1)") (class "Default")
      (node (ref "J8") (pin "1") (pinfunction "1_1") (pintype "passive"))
      (node (ref "R95") (pin "2") (pinfunction "2_2") (pintype "passive"))
    )
    (net (code "95") (name "Net-(Q1-B)") (class "Default")
      (node (ref "Q1") (pin "1") (pinfunction "B_1") (pintype "passive"))
      (node (ref "R1") (pin "2") (pinfunction "2_2") (pintype "passive"))
    )
    (net (code "96") (name "Net-(Q1-C)") (class "Default")
      (node (ref "Q1") (pin "3") (pinfunction "C_3") (pintype "passive"))
      (node (ref "R9") (pin "1") (pinfunction "1_1") (pintype "passive"))
    )
    (net (code "97") (name "Net-(Q3-B)") (class "Default")
      (node (ref "Q3") (pin "1") (pinfunction "B_1") (pintype "passive"))
      (node (ref "R14") (pin "2") (pinfunction "2_2") (pintype "passive"))
    )
    (net (code "98") (name "Net-(Q3-C)") (class "Default")
      (node (ref "Q3") (pin "3") (pinfunction "C_3") (pintype "passive"))
      (node (ref "R1") (pin "1") (pinfunction "1_1") (pintype "passive"))
      (node (ref "R10") (pin "1") (pinfunction "1_1") (pintype "passive"))
    )
    (net (code "99") (name "Net-(Q4-B)") (class "Default")
      (node (ref "Q4") (pin "1") (pinfunction "B_1") (pintype "passive"))
      (node (ref "R25") (pin "1") (pinfunction "1_1") (pintype "passive"))
    )
    (net (code "100") (name "Net-(Q4-C)") (class "Default")
      (node (ref "D5") (pin "1") (pinfunction "1_1") (pintype "passive"))
      (node (ref "Q4") (pin "3") (pinfunction "C_3") (pintype "passive"))
      (node (ref "R16") (pin "2") (pinfunction "2_2") (pintype "passive"))
    )
    (net (code "101") (name "Net-(Q6-B)") (class "Default")
      (node (ref "Q6") (pin "1") (pinfunction "B_1") (pintype "passive"))
      (node (ref "R20") (pin "2") (pinfunction "2_2") (pintype "passive"))
    )
    (net (code "102") (name "Net-(Q6-C)") (class "Default")
      (node (ref "C58") (pin "1") (pinfunction "1_1") (pintype "passive"))
      (node (ref "Q6") (pin "3") (pinfunction "C_3") (pintype "passive"))
      (node (ref "R22") (pin "1") (pinfunction "1_1") (pintype "passive"))
      (node (ref "U9") (pin "8") (pinfunction "VCC_8") (pintype "passive"))
    )
    (net (code "103") (name "Net-(Q7-B)") (class "Default")
      (node (ref "C11") (pin "1") (pinfunction "1_1") (pintype "passive"))
      (node (ref "Q7") (pin "1") (pinfunction "B_1") (pintype "passive"))
      (node (ref "R19") (pin "1") (pinfunction "1_1") (pintype "passive"))
      (node (ref "R5") (pin "2") (pinfunction "2_2") (pintype "passive"))
    )
    (net (code "104") (name "Net-(Q8-B)") (class "Default")
      (node (ref "Q8") (pin "1") (pinfunction "B_1") (pintype "passive"))
      (node (ref "R33") (pin "2") (pinfunction "2_2") (pintype "passive"))
    )
    (net (code "105") (name "Net-(Q8-C)") (class "Default")
      (node (ref "Q8") (pin "3") (pinfunction "C_3") (pintype "passive"))
      (node (ref "R24") (pin "1") (pinfunction "1_1") (pintype "passive"))
    )
    (net (code "106") (name "Net-(Q9-B)") (class "Default")
      (node (ref "Q9") (pin "1") (pinfunction "B_1") (pintype "passive"))
      (node (ref "R3") (pin "2") (pinfunction "2_2") (pintype "passive"))
    )
    (net (code "107") (name "Net-(Q9-E)") (class "Default")
      (node (ref "Q9") (pin "2") (pinfunction "E_2") (pintype "passive"))
      (node (ref "R15") (pin "1") (pinfunction "1_1") (pintype "passive"))
    )
    (net (code "108") (name "Net-(Q10-B)") (class "Default")
      (node (ref "Q10") (pin "1") (pinfunction "B_1") (pintype "passive"))
      (node (ref "R12") (pin "2") (pinfunction "2_2") (pintype "passive"))
    )
    (net (code "109") (name "Net-(Q10-C)") (class "Default")
      (node (ref "C36") (pin "1") (pinfunction "1_1") (pintype "passive"))
      (node (ref "Q10") (pin "3") (pinfunction "C_3") (pintype "passive"))
      (node (ref "U1") (pin "3") (pinfunction "WP#_3") (pintype "passive"))
      (node (ref "U1") (pin "7") (pinfunction "HOLD#_7") (pintype "passive"))
      (node (ref "U1") (pin "8") (pinfunction "VDD_8") (pintype "passive"))
    )
    (net (code "110") (name "Net-(Q11-B)") (class "Default")
      (node (ref "Q11") (pin "1") (pinfunction "B_1") (pintype "passive"))
      (node (ref "R38") (pin "2") (pinfunction "2_2") (pintype "passive"))
    )
    (net (code "111") (name "Net-(Q13-B)") (class "Default")
      (node (ref "Q13") (pin "1") (pinfunction "B_1") (pintype "passive"))
      (node (ref "R34") (pin "2") (pinfunction "2_2") (pintype "passive"))
    )
    (net (code "112") (name "Net-(Q13-C)") (class "Default")
      (node (ref "C65") (pin "2") (pinfunction "2_2") (pintype "passive"))
      (node (ref "Q13") (pin "3") (pinfunction "C_3") (pintype "passive"))
      (node (ref "R32") (pin "2") (pinfunction "2_2") (pintype "passive"))
      (node (ref "U11") (pin "3") (pinfunction "VCC_3") (pintype "passive"))
    )
    (net (code "113") (name "Net-(Q14-B)") (class "Default")
      (node (ref "Q14") (pin "1") (pinfunction "B_1") (pintype "passive"))
      (node (ref "R36") (pin "2") (pinfunction "2_2") (pintype "passive"))
    )
    (net (code "114") (name "Net-(Q14-C)") (class "Default")
      (node (ref "Q14") (pin "3") (pinfunction "C_3") (pintype "passive"))
      (node (ref "R26") (pin "1") (pinfunction "1_1") (pintype "passive"))
      (node (ref "R33") (pin "1") (pinfunction "1_1") (pintype "passive"))
    )
    (net (code "115") (name "Net-(Q15-G)") (class "Default")
      (node (ref "Q15") (pin "1") (pinfunction "G_1") (pintype "passive"))
      (node (ref "R18") (pin "2") (pinfunction "2_2") (pintype "passive"))
      (node (ref "R6") (pin "1") (pinfunction "1_1") (pintype "passive"))
    )
    (net (code "116") (name "Net-(Q15-S)") (class "Default")
      (node (ref "C21") (pin "1") (pinfunction "1_1") (pintype "passive"))
      (node (ref "Q15") (pin "2") (pinfunction "S_2") (pintype "passive"))
      (node (ref "R50") (pin "2") (pinfunction "2_2") (pintype "passive"))
      (node (ref "R6") (pin "2") (pinfunction "2_2") (pintype "passive"))
      (node (ref "U6") (pin "3") (pinfunction "Vout_3") (pintype "passive"))
    )
    (net (code "117") (name "Net-(Q16-B)") (class "Default")
      (node (ref "Q16") (pin "1") (pinfunction "B_1") (pintype "passive"))
      (node (ref "R39") (pin "1") (pinfunction "1_1") (pintype "passive"))
      (node (ref "R40") (pin "2") (pinfunction "2_2") (pintype "passive"))
    )
    (net (code "118") (name "Net-(Q16-C)") (class "Default")
      (node (ref "Q16") (pin "3") (pinfunction "C_3") (pintype "passive"))
      (node (ref "R41") (pin "2") (pinfunction "2_2") (pintype "passive"))
    )
    (net (code "119") (name "Net-(Q20-B)") (class "Default")
      (node (ref "Q20") (pin "1") (pinfunction "B_1") (pintype "passive"))
      (node (ref "R41") (pin "1") (pinfunction "1_1") (pintype "passive"))
      (node (ref "R43") (pin "2") (pinfunction "2_2") (pintype "passive"))
    )
    (net (code "120") (name "Net-(Q22-B)") (class "Default")
      (node (ref "Q22") (pin "1") (pinfunction "B_1") (pintype "passive"))
      (node (ref "R61") (pin "1") (pinfunction "1_1") (pintype "passive"))
    )
    (net (code "121") (name "Net-(Q22-E)") (class "Default")
      (node (ref "Q22") (pin "2") (pinfunction "E_2") (pintype "passive"))
      (node (ref "R58") (pin "2") (pinfunction "2_2") (pintype "passive"))
      (node (ref "R59") (pin "1") (pinfunction "1_1") (pintype "passive"))
    )
    (net (code "122") (name "Net-(U2-Vin)") (class "Default")
      (node (ref "C4") (pin "1") (pinfunction "1_1") (pintype "passive"))
      (node (ref "D2") (pin "2") (pinfunction "2_2") (pintype "passive"))
      (node (ref "R42") (pin "1") (pinfunction "1_1") (pintype "passive"))
      (node (ref "U2") (pin "2") (pinfunction "Vin_2") (pintype "passive"))
    )
    (net (code "123") (name "Net-(U7-VDD15)") (class "Default")
      (node (ref "C38") (pin "1") (pinfunction "1_1") (pintype "passive"))
      (node (ref "U7") (pin "62") (pinfunction "VDD15_62") (pintype "passive"))
    )
    (net (code "124") (name "Net-(U11-OUT)") (class "Default")
      (node (ref "R31") (pin "1") (pinfunction "1_1") (pintype "passive"))
      (node (ref "U11") (pin "1") (pinfunction "OUT_1") (pintype "passive"))
    )
    (net (code "125") (name "Net-(U20-SDO)") (class "Default")
      (node (ref "R96") (pin "1") (pinfunction "1_1") (pintype "passive"))
      (node (ref "R97") (pin "1") (pinfunction "1_1") (pintype "passive"))
      (node (ref "U20") (pin "8") (pinfunction "SDO_8") (pintype "passive"))
    )
    (net (code "126") (name "VCC") (class "Default")
      (node (ref "C13") (pin "2") (pinfunction "2_2") (pintype "passive"))
      (node (ref "C17") (pin "1") (pinfunction "1_1") (pintype "passive"))
      (node (ref "C18") (pin "1") (pinfunction "1_1") (pintype "passive"))
      (node (ref "C30") (pin "1") (pinfunction "1_1") (pintype "passive"))
      (node (ref "C31") (pin "1") (pinfunction "1_1") (pintype "passive"))
      (node (ref "C44") (pin "2") (pinfunction "2_2") (pintype "passive"))
      (node (ref "C48") (pin "2") (pinfunction "2_2") (pintype "passive"))
      (node (ref "C5") (pin "1") (pinfunction "1_1") (pintype "passive"))
      (node (ref "C6") (pin "1") (pinfunction "1_1") (pintype "passive"))
      (node (ref "D1") (pin "1") (pinfunction "1_1") (pintype "passive"))
      (node (ref "J3") (pin "5") (pinfunction "5_5") (pintype "passive"))
      (node (ref "J8") (pin "5") (pinfunction "5_5") (pintype "passive"))
      (node (ref "Q10") (pin "2") (pinfunction "E_2") (pintype "passive"))
      (node (ref "Q13") (pin "2") (pinfunction "E_2") (pintype "passive"))
      (node (ref "Q16") (pin "2") (pinfunction "E_2") (pintype "passive"))
      (node (ref "Q4") (pin "2") (pinfunction "E_2") (pintype "passive"))
      (node (ref "Q6") (pin "2") (pinfunction "E_2") (pintype "passive"))
      (node (ref "R27") (pin "2") (pinfunction "2_2") (pintype "passive"))
      (node (ref "R39") (pin "2") (pinfunction "2_2") (pintype "passive"))
      (node (ref "R59") (pin "2") (pinfunction "2_2") (pintype "passive"))
      (node (ref "R93") (pin "1") (pinfunction "1_1") (pintype "passive"))
      (node (ref "R94") (pin "2") (pinfunction "2_2") (pintype "passive"))
      (node (ref "U3") (pin "3") (pinfunction "Vout_3") (pintype "passive"))
      (node (ref "U7") (pin "64") (pinfunction "VDD(VDDA)_64") (pintype "passive"))
      (node (ref "U7") (pin "66") (pinfunction "VREFP_66") (pintype "passive"))
      (node (ref "U7") (pin "67") (pinfunction "VBAT_67") (pintype "passive"))
      (node (ref "U8") (pin "8") (pinfunction "VCC_8") (pintype "passive"))
    )
    (net (code "127") (name "VIN") (class "Default")
      (node (ref "C29") (pin "2") (pinfunction "2_2") (pintype "passive"))
      (node (ref "D2") (pin "1") (pinfunction "1_1") (pintype "passive"))
      (node (ref "D4") (pin "1") (pinfunction "1_1") (pintype "passive"))
      (node (ref "J7") (pin "1") (pinfunction "1_1") (pintype "passive"))
      (node (ref "Q1") (pin "2") (pinfunction "E_2") (pintype "passive"))
      (node (ref "R10") (pin "2") (pinfunction "2_2") (pintype "passive"))
      (node (ref "VIN1") (pin "1") (pinfunction "1_1") (pintype "passive"))
    )
    (net (code "128") (name "VIN2") (class "Default")
      (node (ref "C57") (pin "1") (pinfunction "1_1") (pintype "passive"))
      (node (ref "D7") (pin "1") (pinfunction "A_1") (pintype "passive"))
      (node (ref "D7") (pin "2") (pinfunction "A_2") (pintype "passive"))
      (node (ref "D9") (pin "1") (pinfunction "1_1") (pintype "passive"))
      (node (ref "J4") (pin "1") (pinfunction "1_1") (pintype "passive"))
      (node (ref "Q8") (pin "2") (pinfunction "E_2") (pintype "passive"))
      (node (ref "R26") (pin "2") (pinfunction "2_2") (pintype "passive"))
      (node (ref "VIN2") (pin "1") (pinfunction "1_1") (pintype "passive"))
    )
    (net (code "129") (name "VIN_NB") (class "Default")
      (node (ref "C15") (pin "1") (pinfunction "1_1") (pintype "passive"))
      (node (ref "C23") (pin "1") (pinfunction "1_1") (pintype "passive"))
      (node (ref "D4") (pin "2") (pinfunction "2_2") (pintype "passive"))
      (node (ref "D8") (pin "2") (pinfunction "2_2") (pintype "passive"))
      (node (ref "D9") (pin "2") (pinfunction "2_2") (pintype "passive"))
      (node (ref "R50") (pin "1") (pinfunction "1_1") (pintype "passive"))
      (node (ref "U6") (pin "2") (pinfunction "Vin_2") (pintype "passive"))
    )
    (net (code "130") (name "unconnected-(U9-NC-Pad2)") (class "Default")
      (node (ref "U9") (pin "2") (pinfunction "NC_2") (pintype "passive"))
    )
    (net (code "131") (name "unconnected-(U9-NC-Pad4)") (class "Default")
      (node (ref "U9") (pin "4") (pinfunction "NC_4") (pintype "passive"))
    )
    (net (code "132") (name "unconnected-(U9-NC-Pad5)") (class "Default")
      (node (ref "U9") (pin "5") (pinfunction "NC_5") (pintype "passive"))
    )
    (net (code "133") (name "unconnected-(U20-CSB-Pad7)") (class "Default")
      (node (ref "U20") (pin "7") (pinfunction "CSB_7") (pintype "passive"))
    )
    (net (code "134") (name "unconnected-(U20-NC-Pad4)") (class "Default")
      (node (ref "U20") (pin "4") (pinfunction "NC_4") (pintype "passive+no_connect"))
    )
  )
)
